# cnc_1_0_0.net
KiCad netlist of a schematic drawn in EAGLE
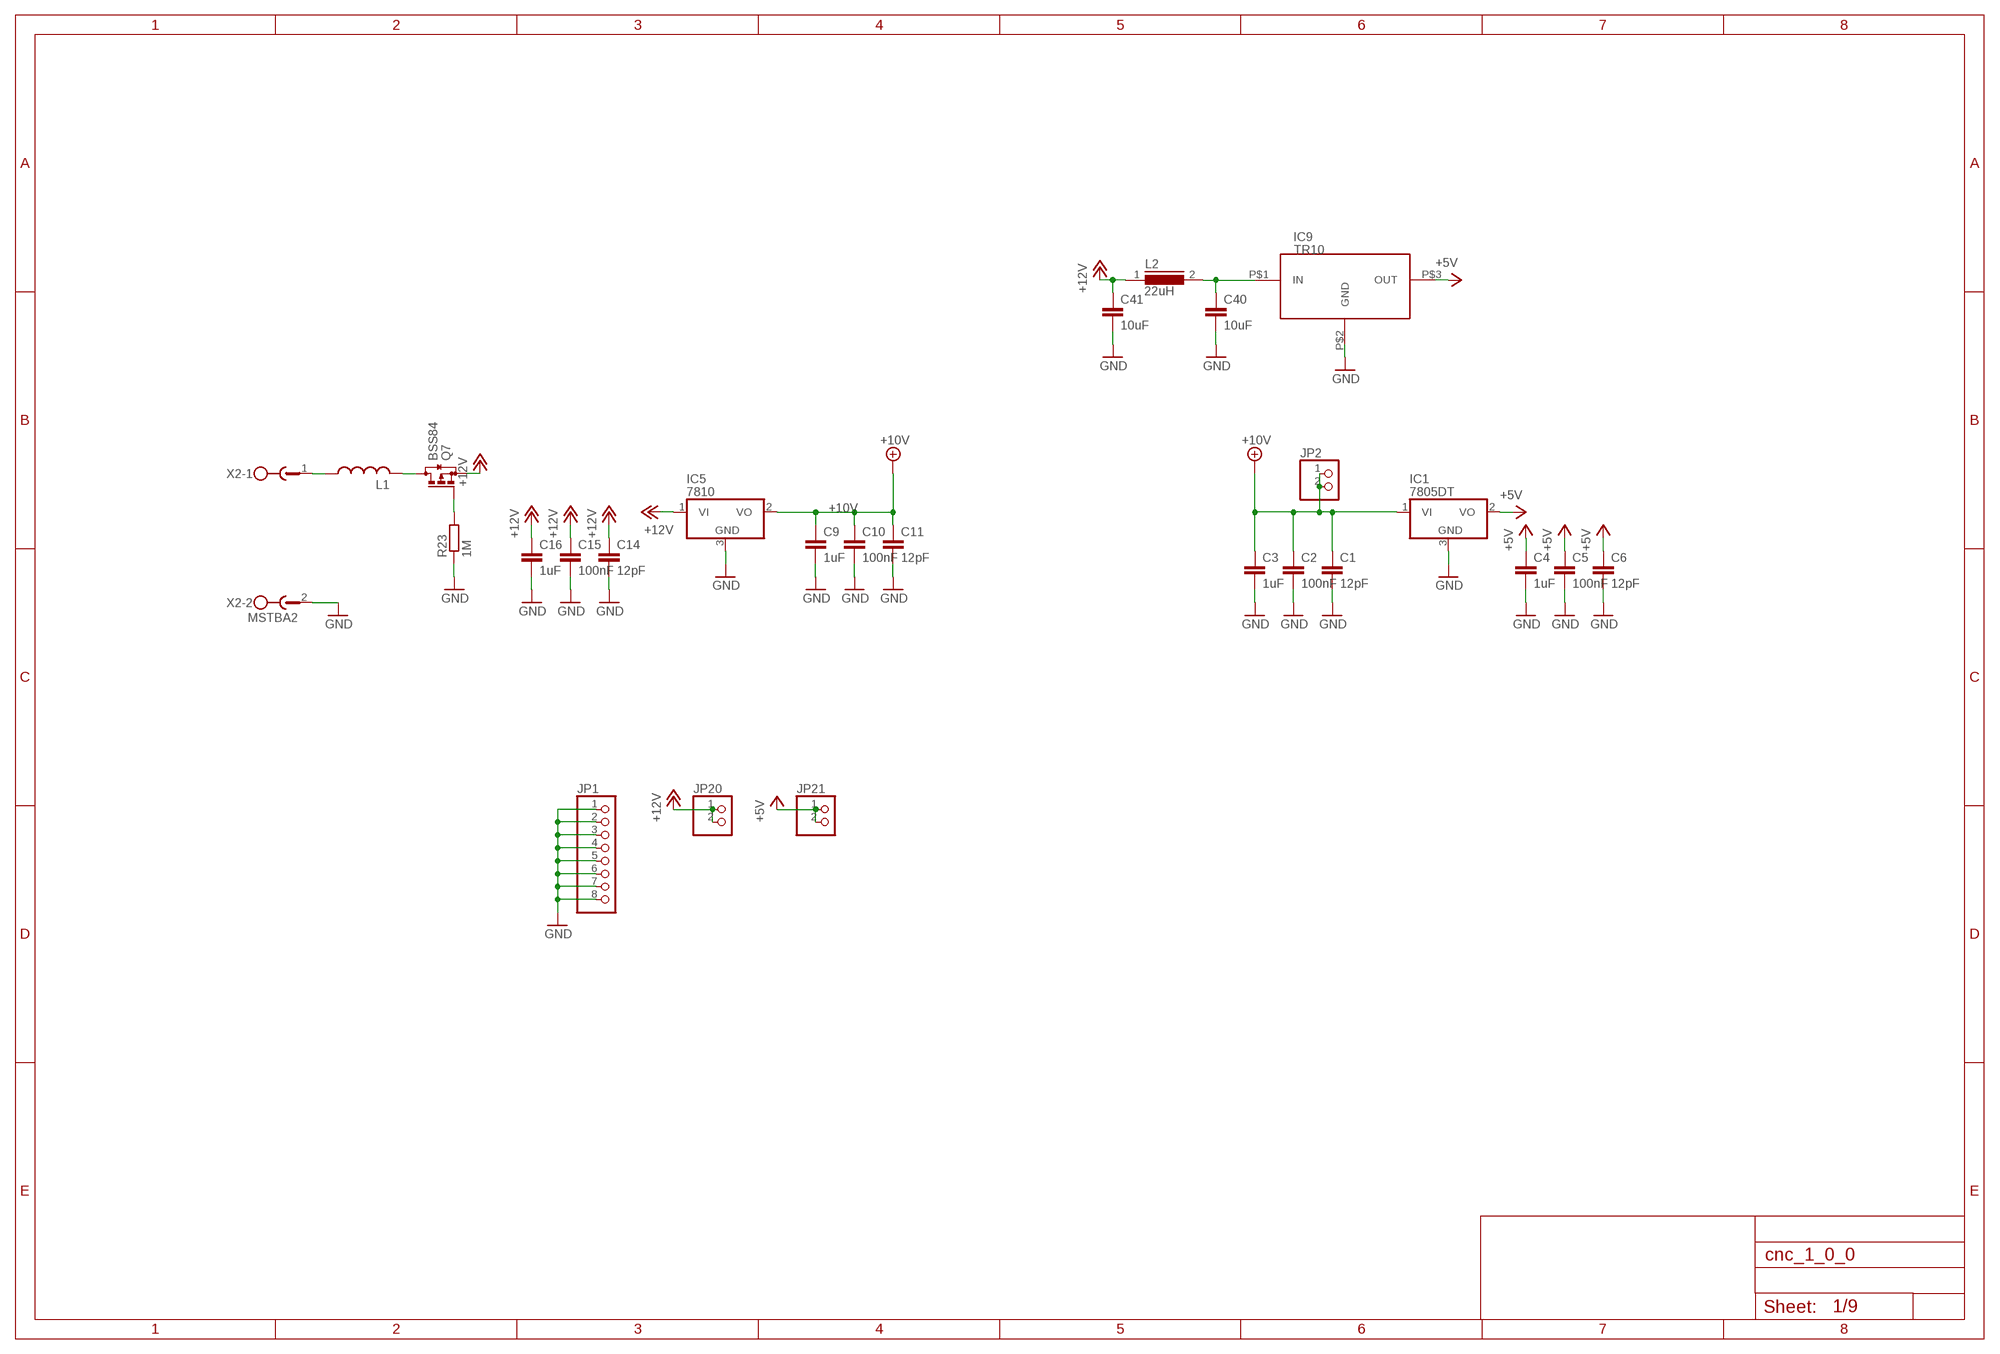
[diagram p0: schematic, sheet 1]
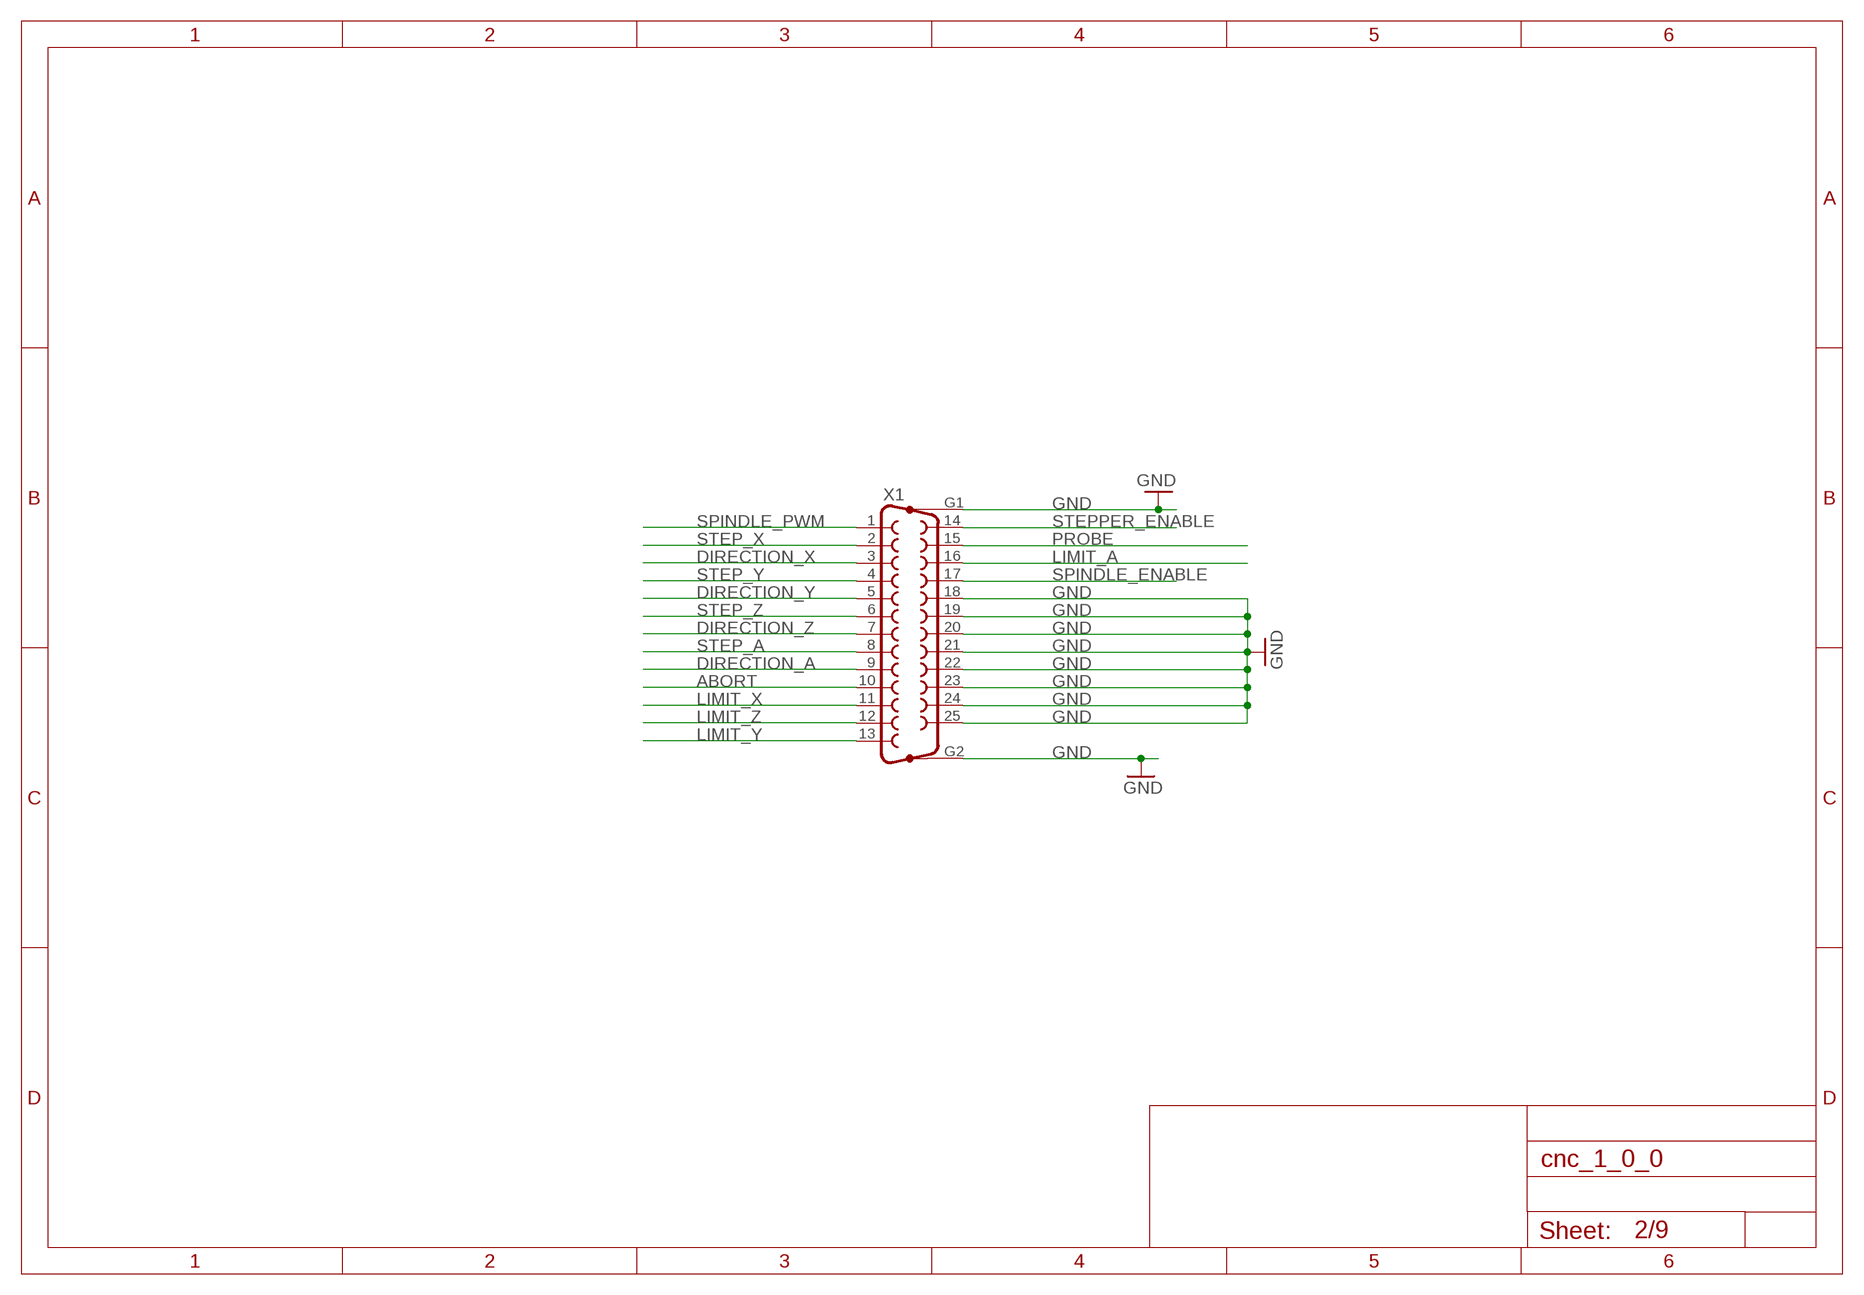
[diagram p1: schematic, sheet 2]
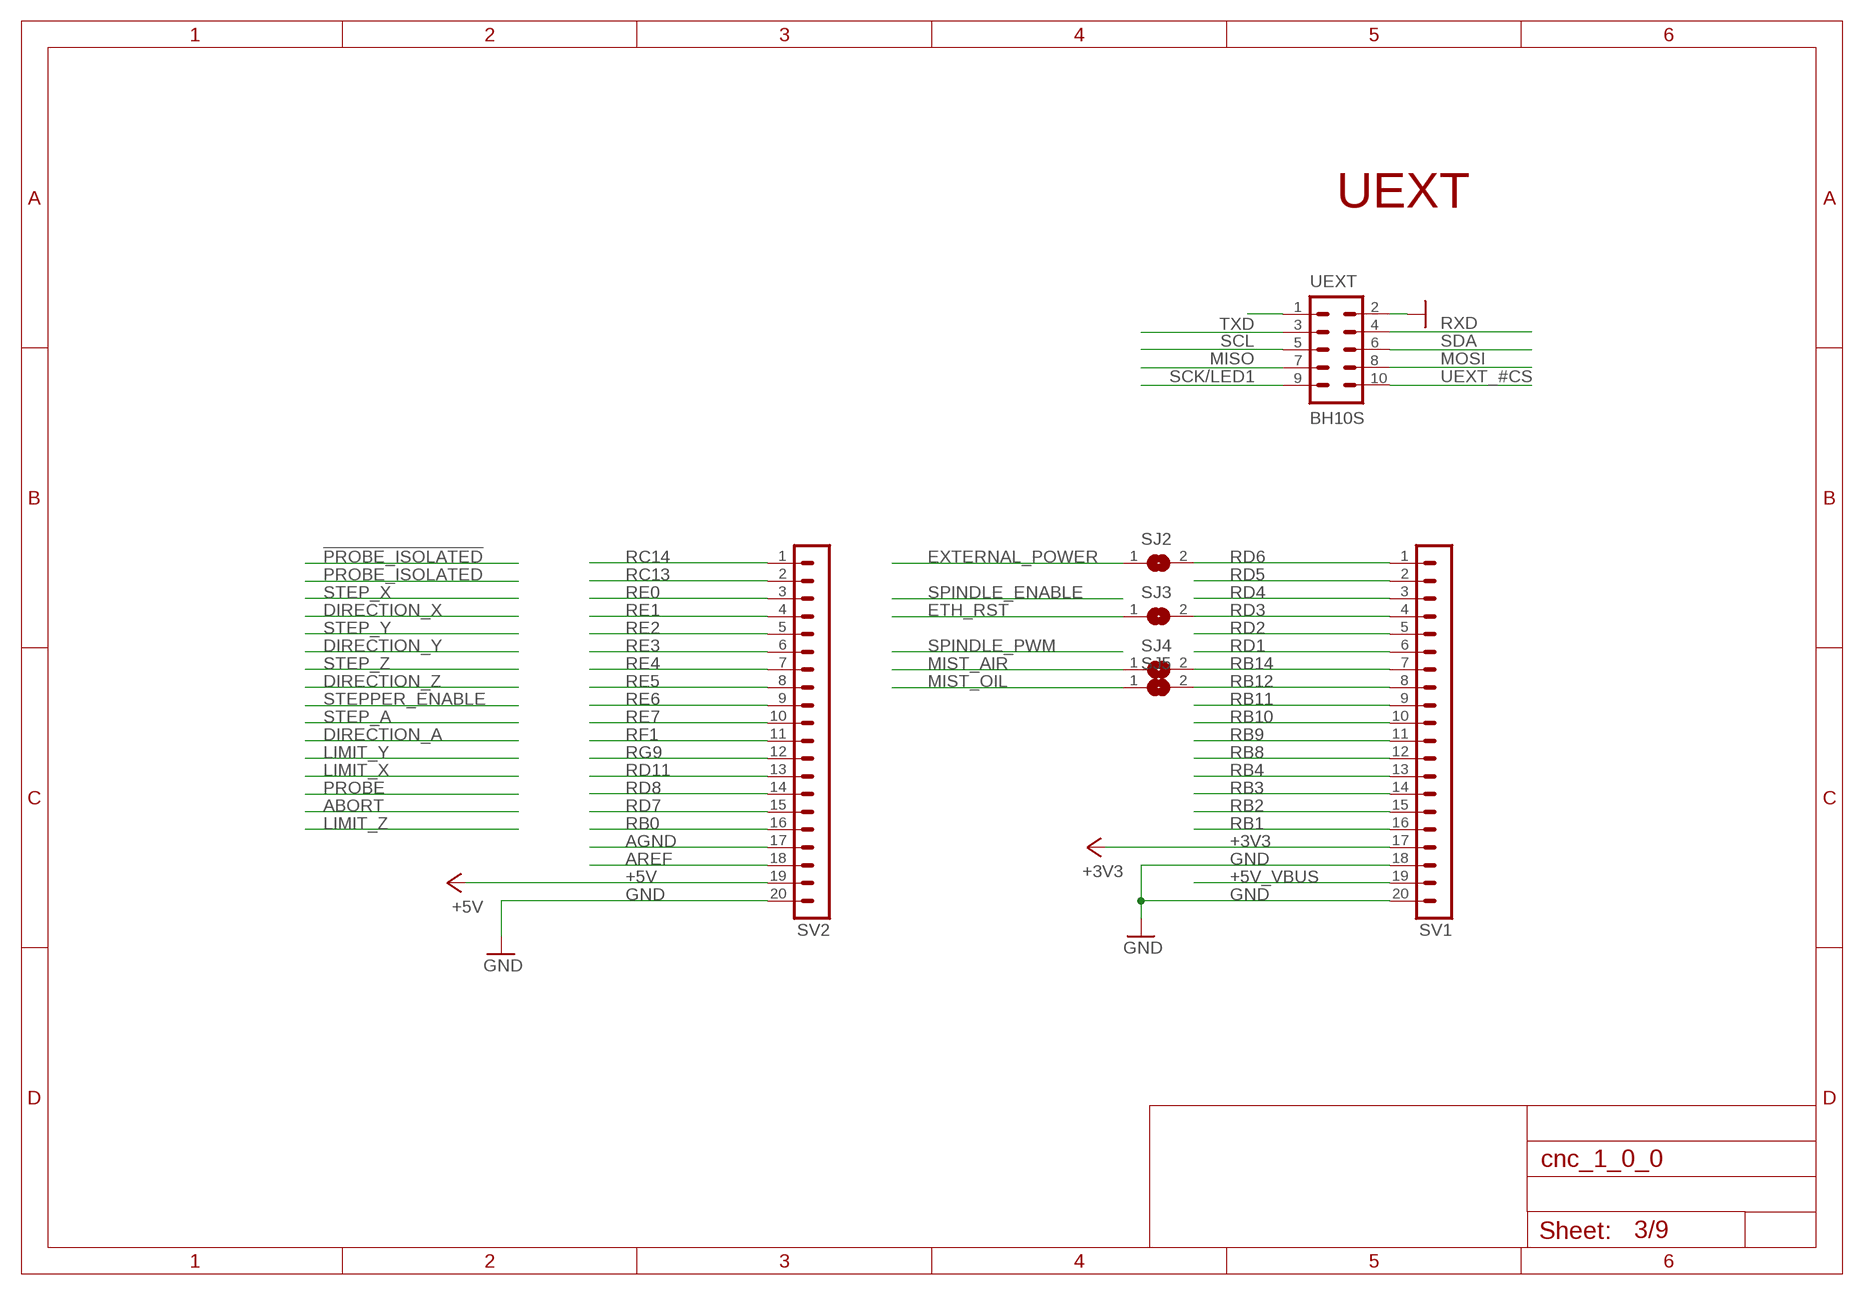
[diagram p2: schematic, sheet 3]
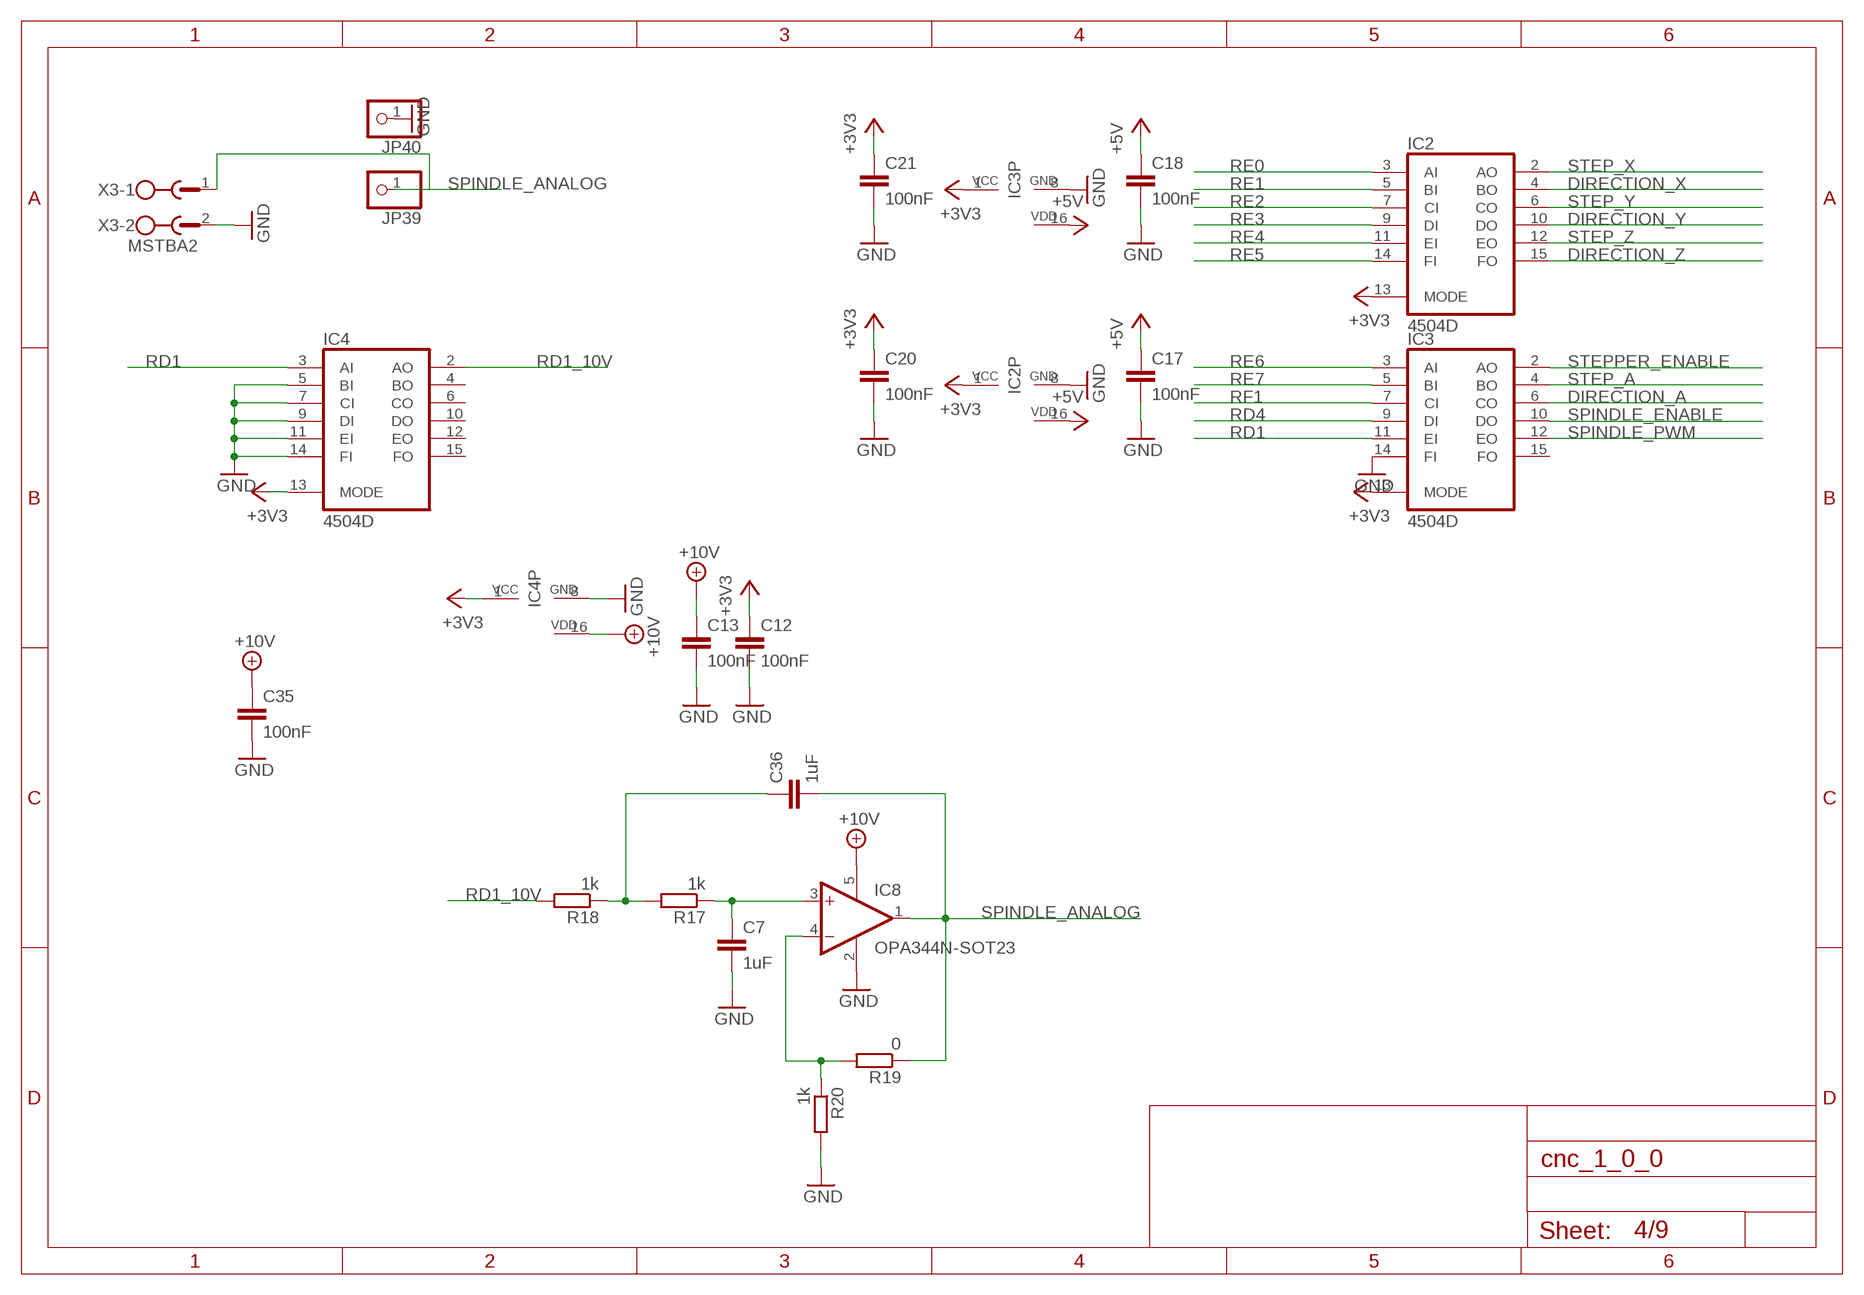
[diagram p3: schematic, sheet 4]
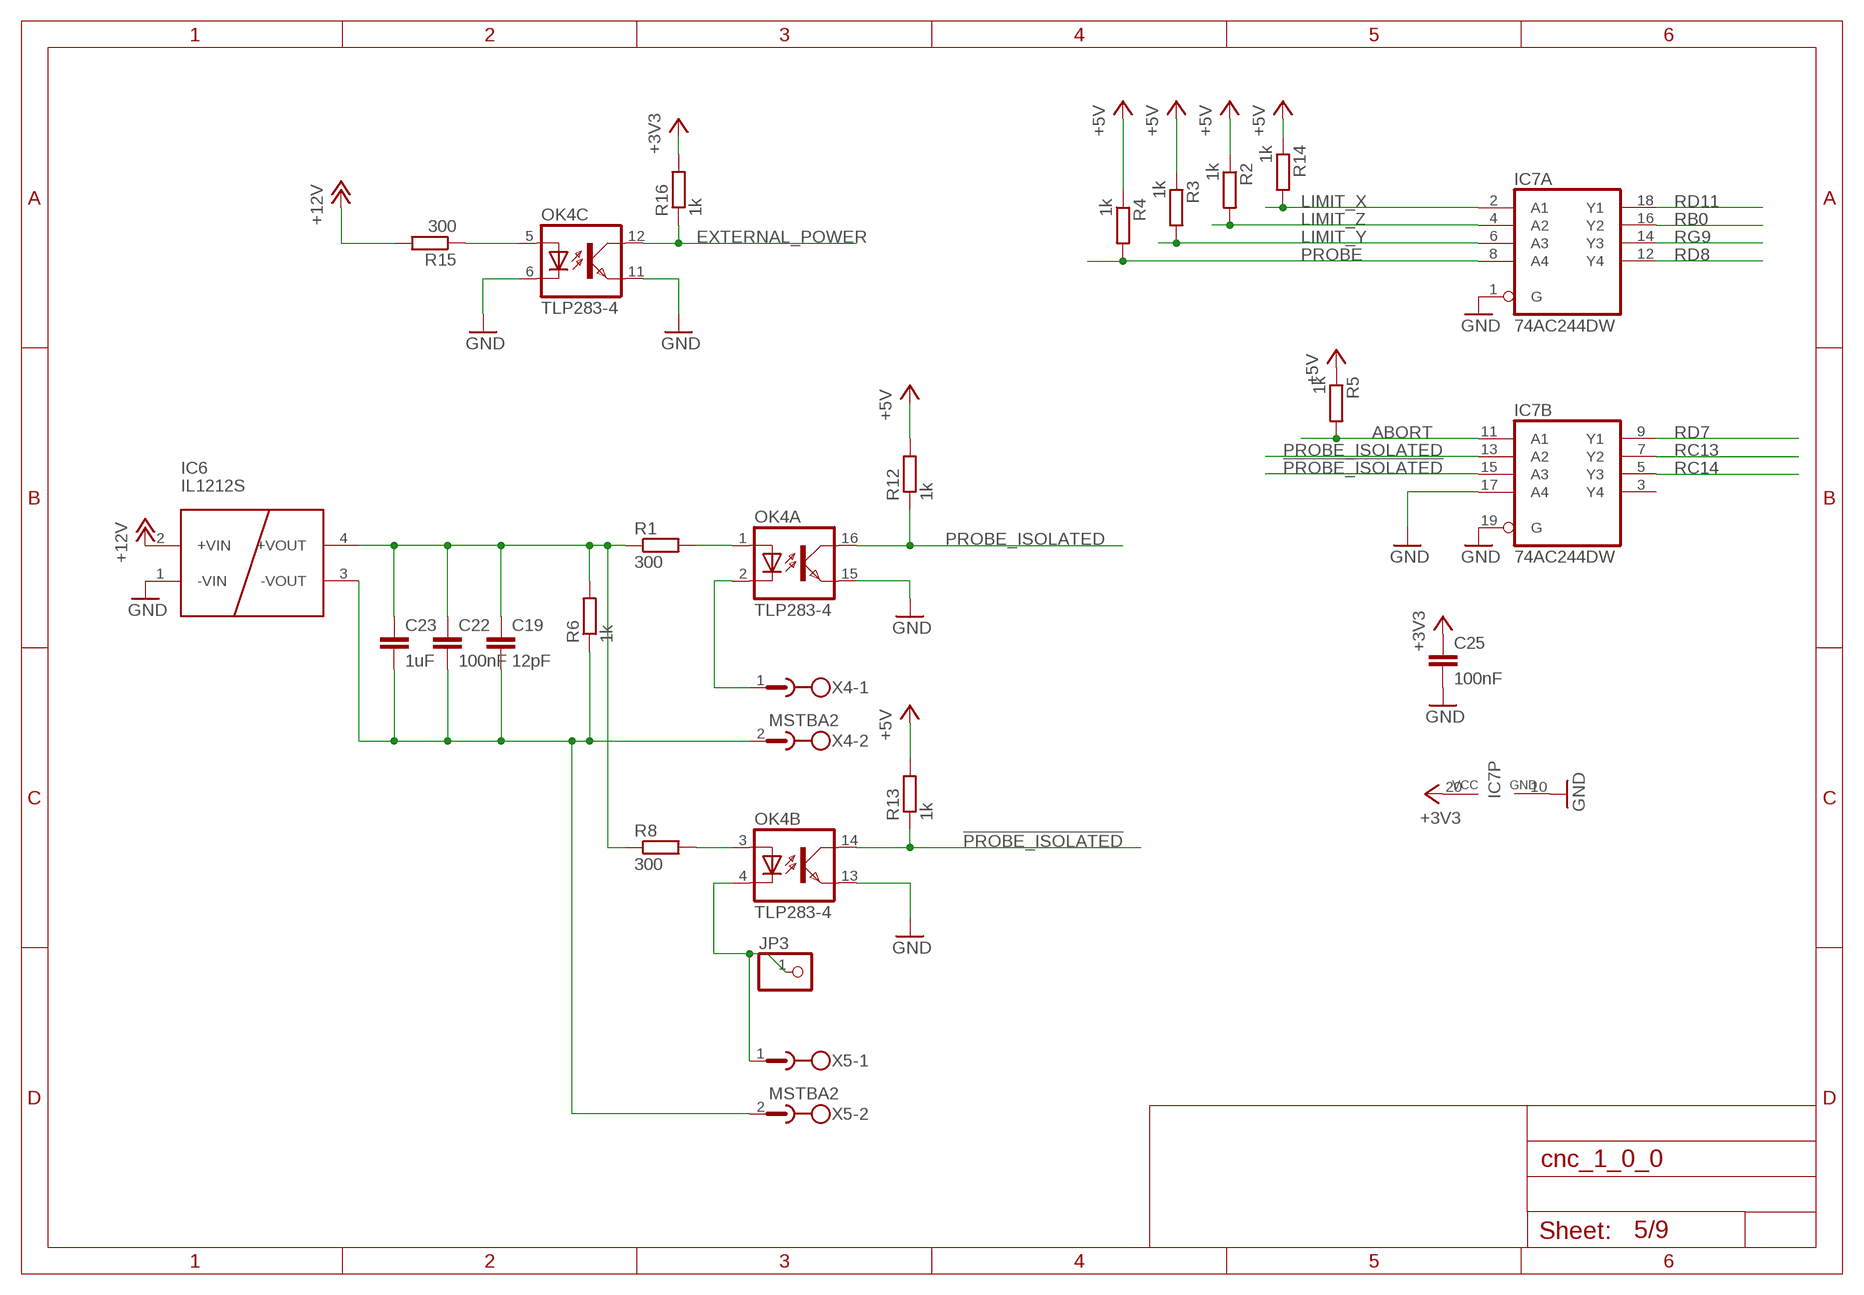
[diagram p4: schematic, sheet 5]
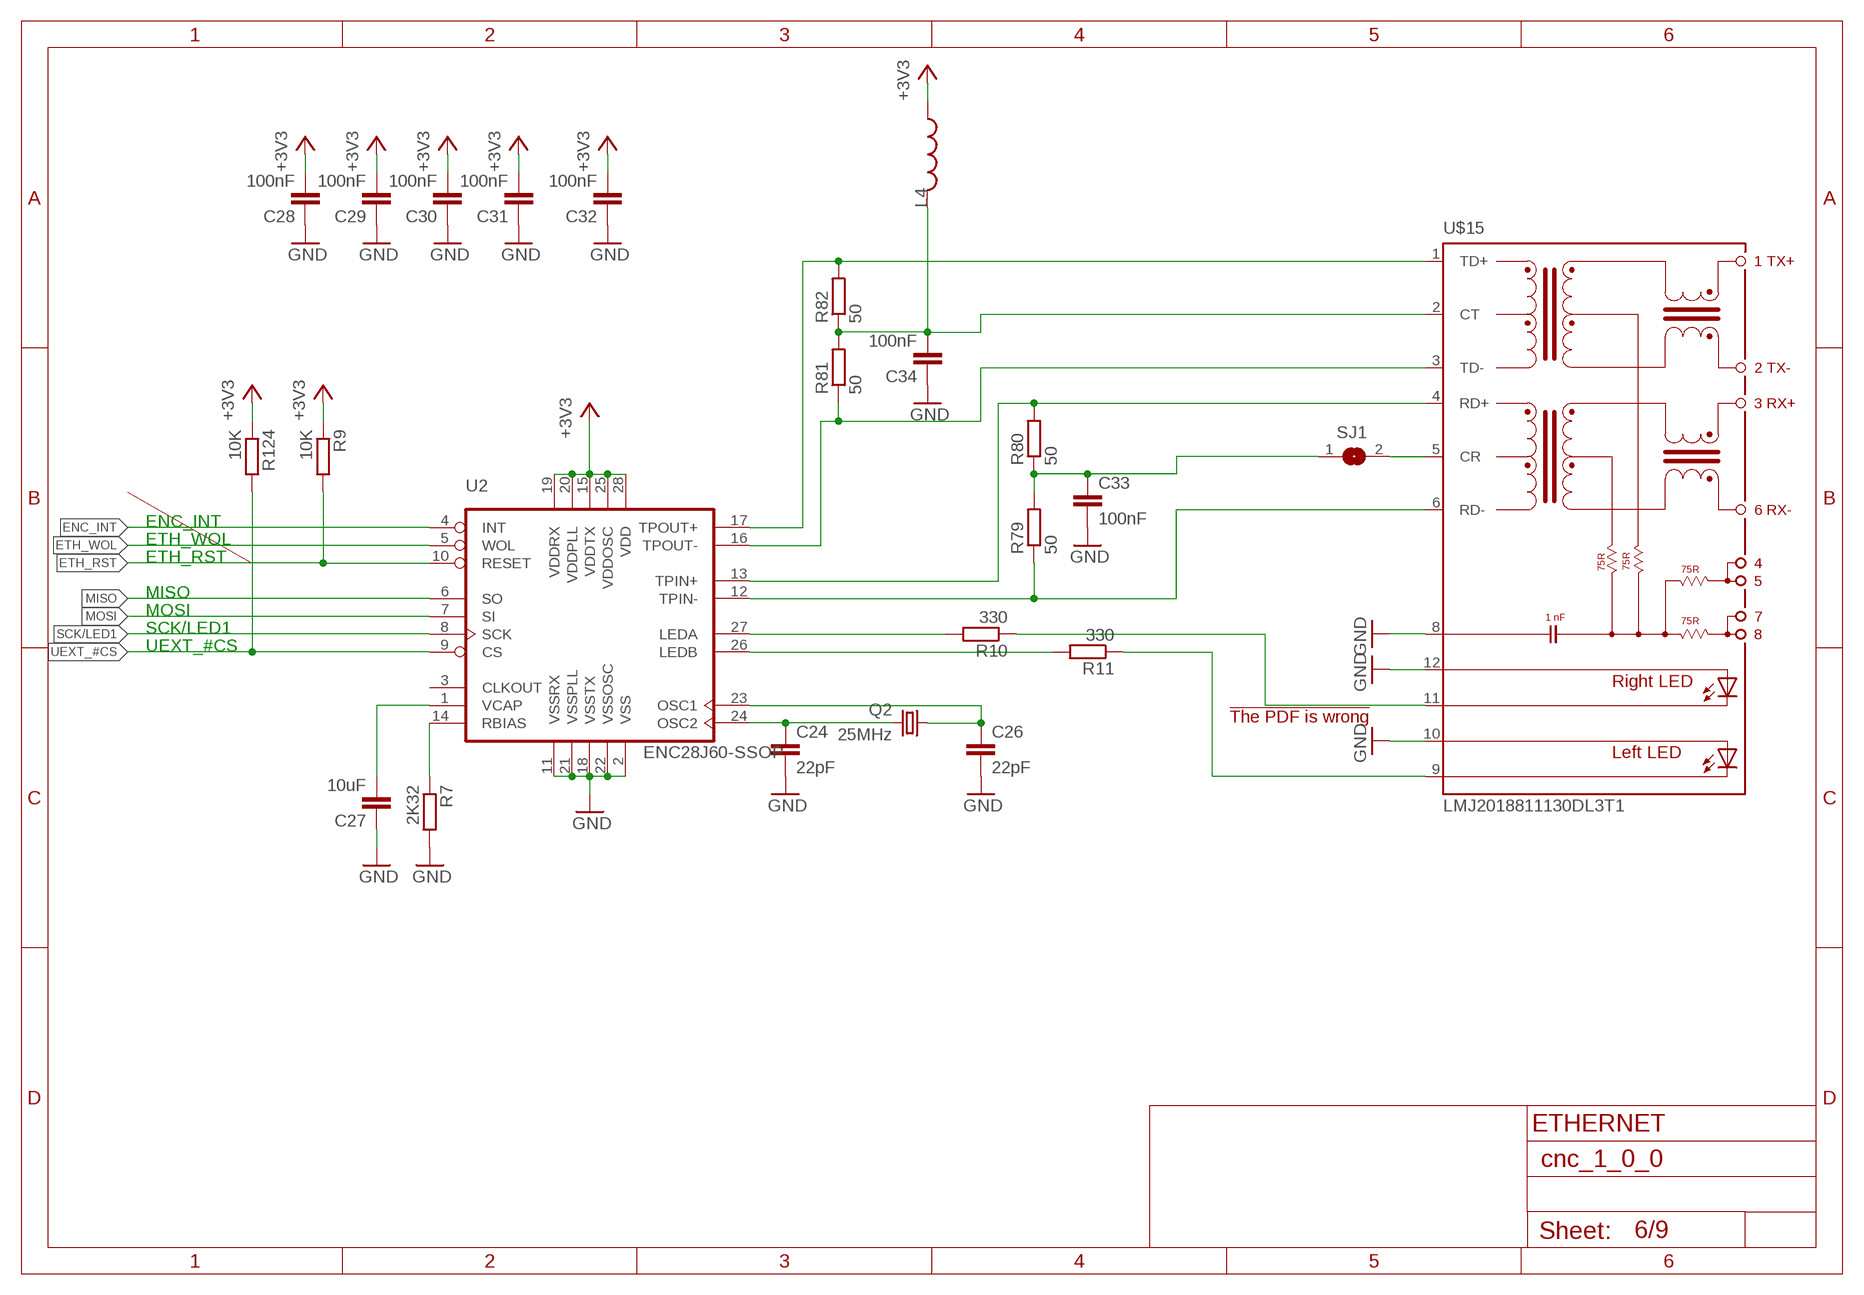
[diagram p5: schematic, sheet 6]
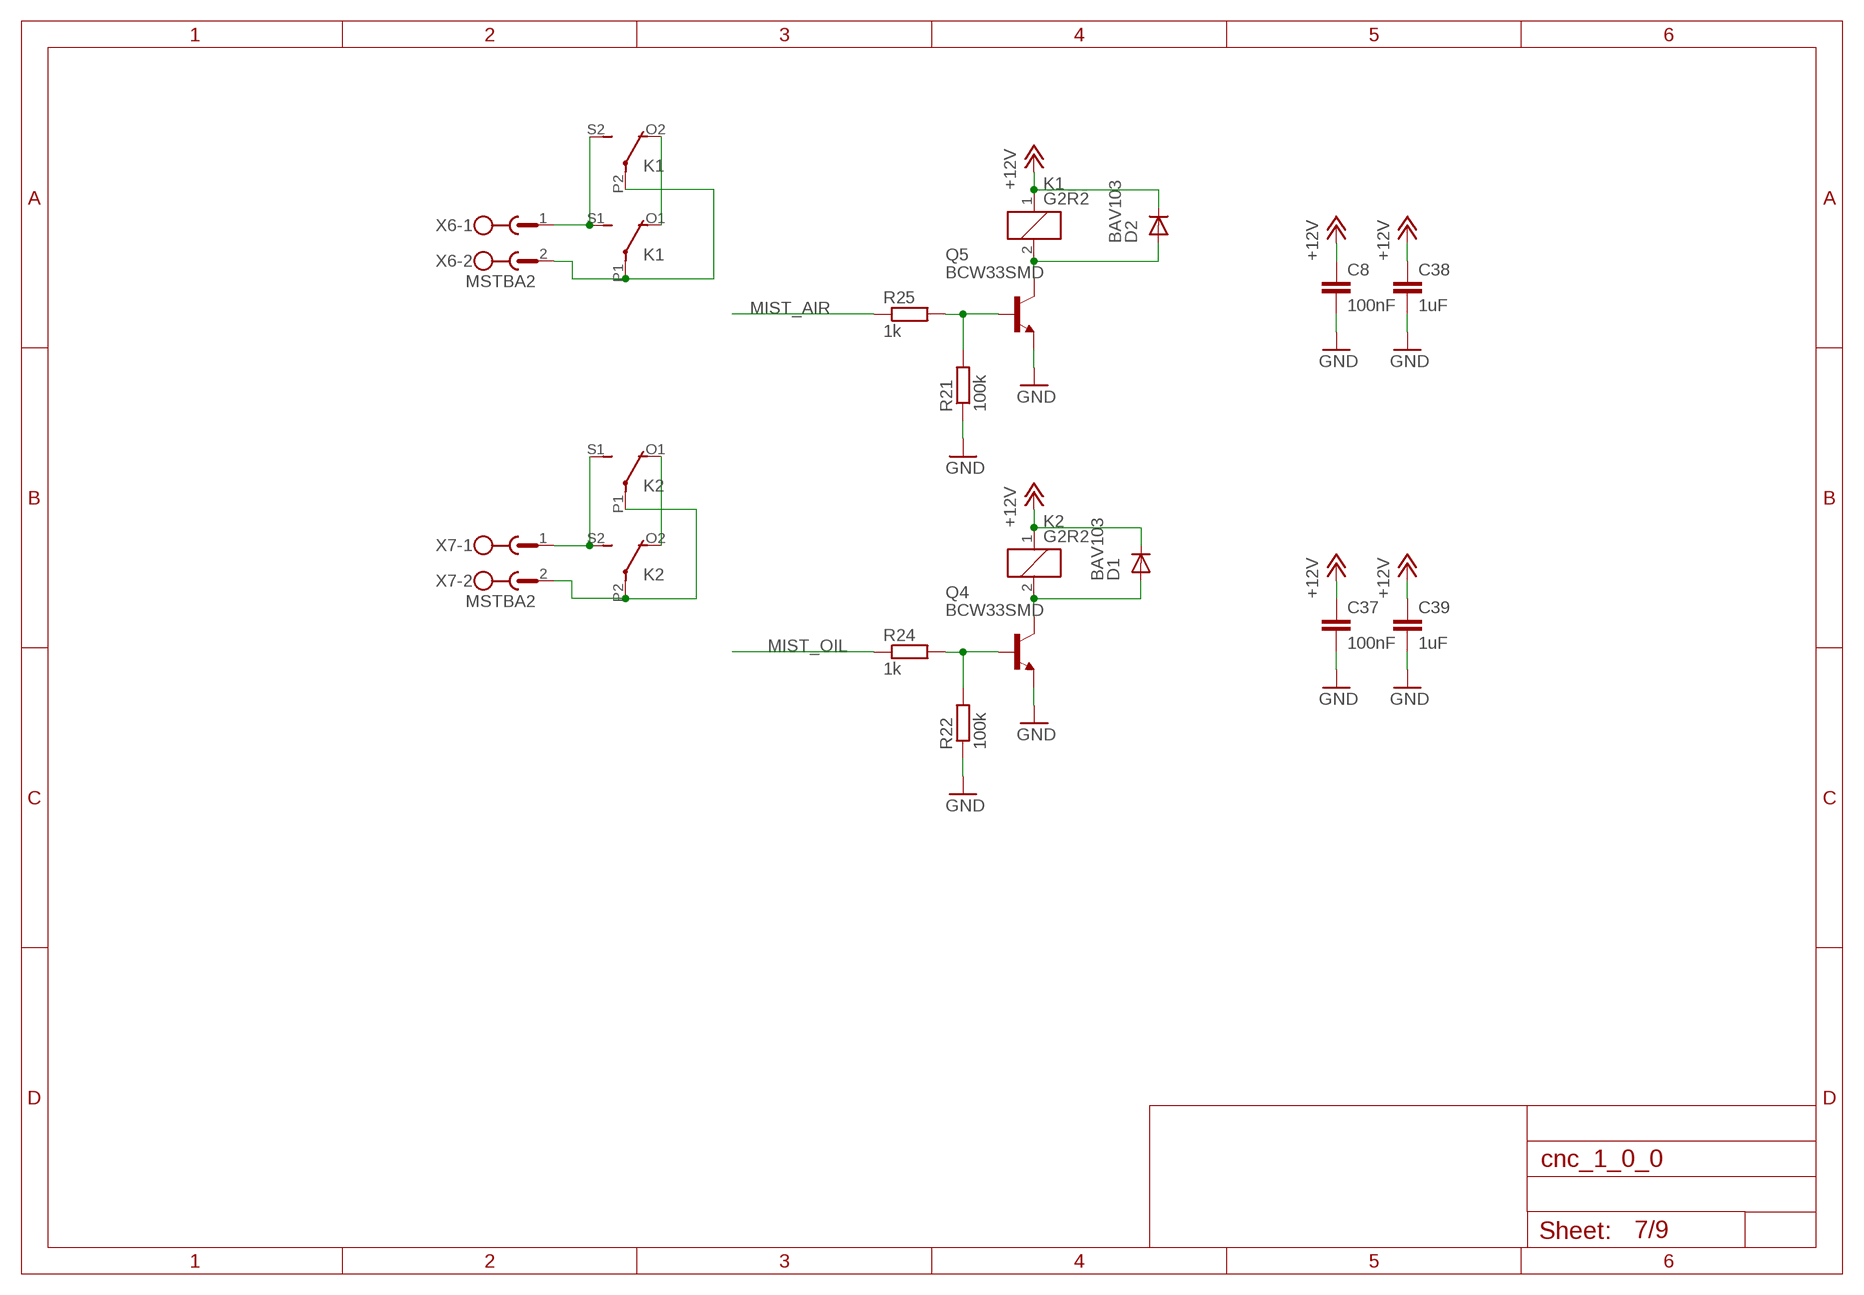
[diagram p6: schematic, sheet 7]
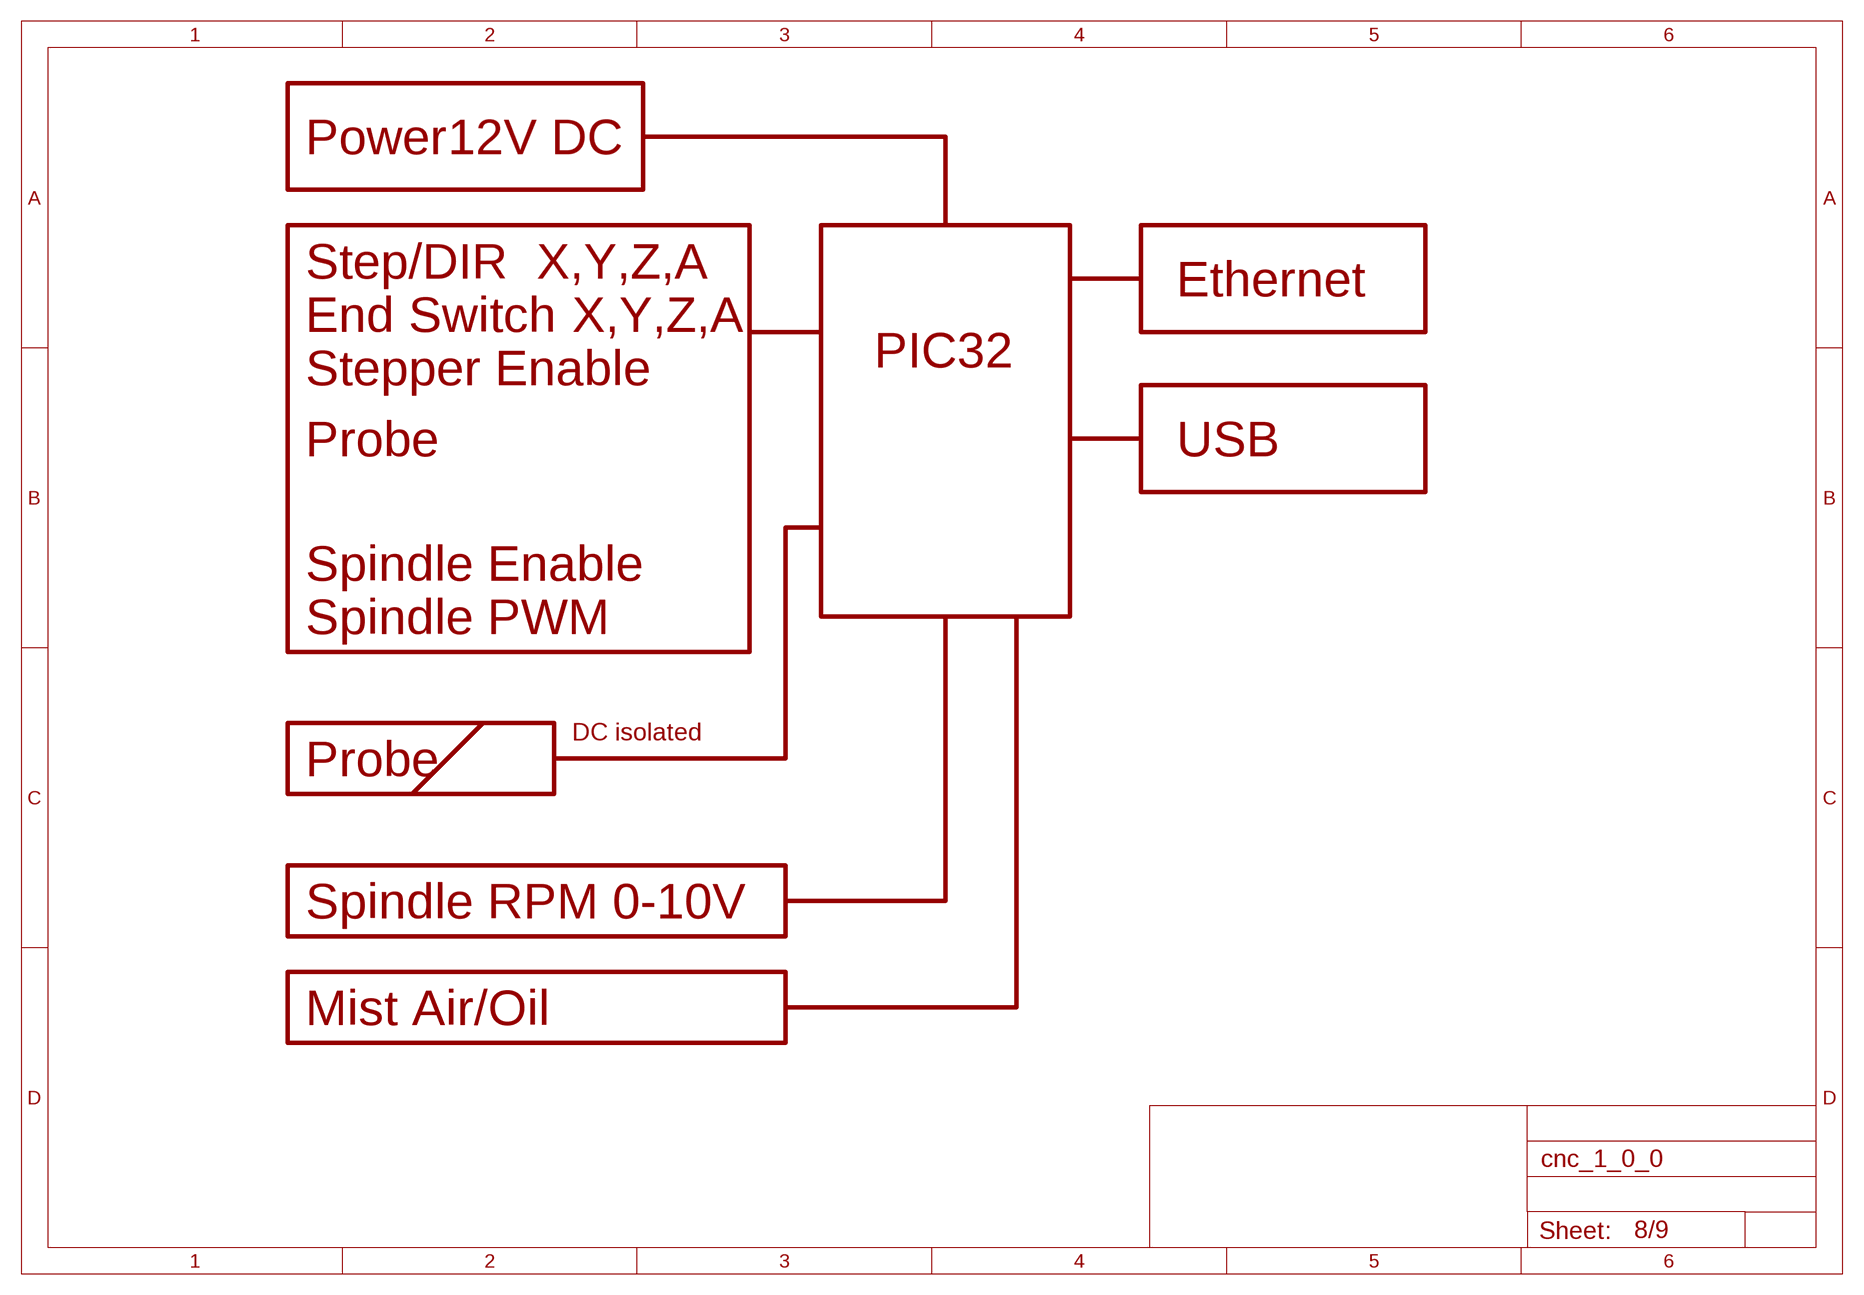
[diagram p7: schematic, sheet 8]
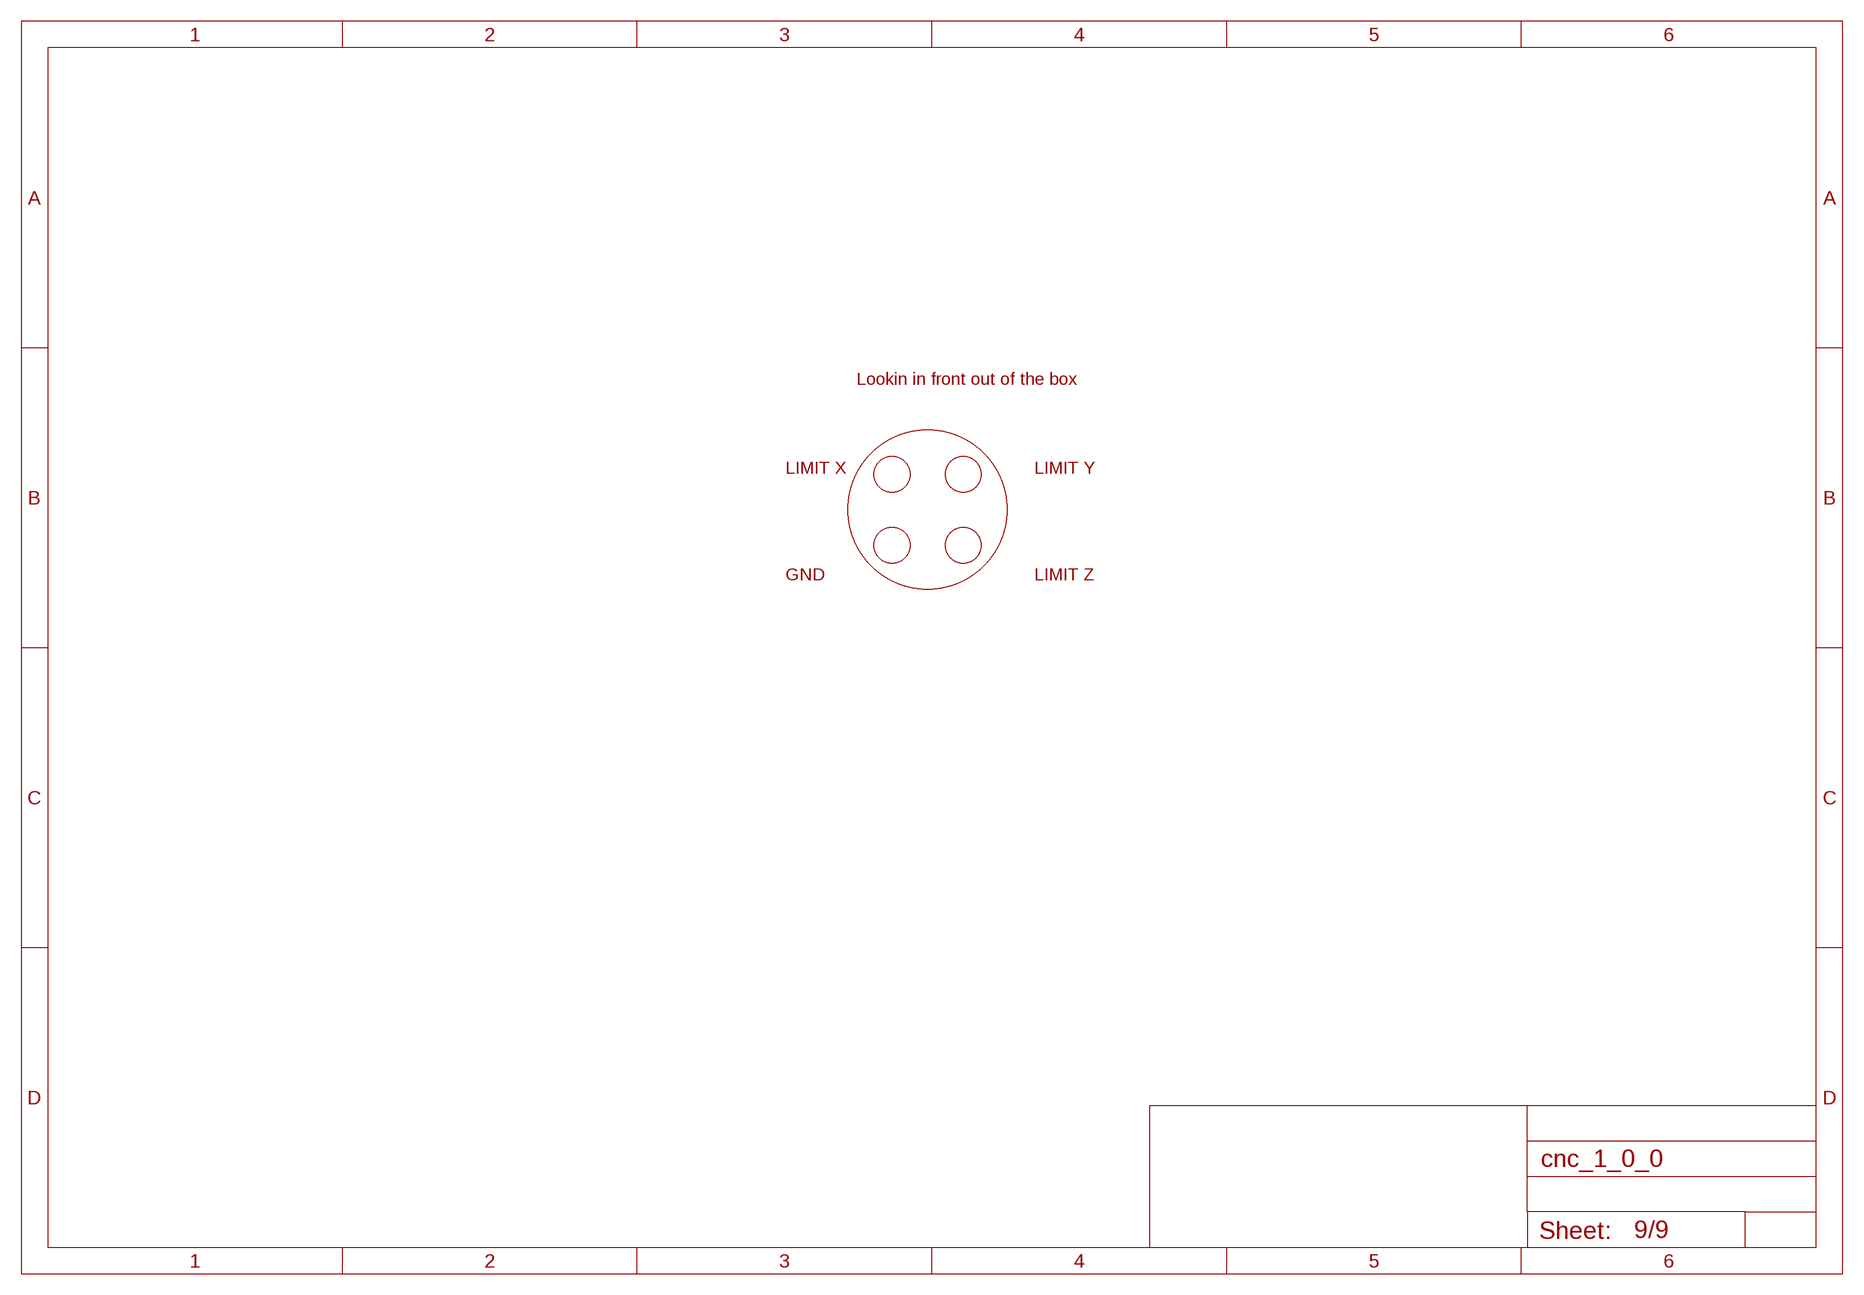
[diagram p8: schematic, sheet 9]

(export (version "E")
  (design (tool "Eeschema 10.0.6"))
  (components
    (comp (ref "SJ2") (value "SJ") (footprint "eagle-import:SJ") (libsource (lib "eagle-import") (part "SJ")))
    (comp (ref "SJ3") (value "SJ") (footprint "eagle-import:SJ") (libsource (lib "eagle-import") (part "SJ")))
    (comp (ref "SJ4") (value "SJ") (footprint "eagle-import:SJ") (libsource (lib "eagle-import") (part "SJ")))
    (comp (ref "SJ5") (value "SJ") (footprint "eagle-import:SJ") (libsource (lib "eagle-import") (part "SJ")))
    (comp (ref "SV1")
      (value "MA20-1")
      (footprint "eagle-import:MA20-1")
      (libsource (lib "eagle-import") (part "MA20-1"))
    )
    (comp (ref "SV2")
      (value "MA20-1")
      (footprint "eagle-import:MA20-1")
      (libsource (lib "eagle-import") (part "MA20-1"))
    )
    (comp (ref "UEXT")
      (value "BH10S")
      (footprint "eagle-import:ML10-MALE")
      (libsource (lib "eagle-import") (part "ML10"))
    )
    (comp (ref "C19")
      (value "12pF")
      (footprint "eagle-import:C0805K")
      (libsource (lib "eagle-import") (part "C-EUC0805K"))
    )
    (comp (ref "C22")
      (value "100nF")
      (footprint "eagle-import:C0805K")
      (libsource (lib "eagle-import") (part "C-EUC0805K"))
    )
    (comp (ref "C23")
      (value "1uF")
      (footprint "eagle-import:C0805K")
      (libsource (lib "eagle-import") (part "C-EUC0805K"))
    )
    (comp (ref "C25")
      (value "100nF")
      (footprint "eagle-import:C0805K")
      (libsource (lib "eagle-import") (part "C-EUC0805K"))
    )
    (comp (ref "IC6")
      (value "IL1212S")
      (footprint "eagle-import:SIL4")
      (libsource (lib "eagle-import") (part "IL0512S"))
    )
    (comp (ref "IC7")
      (value "74AC244DW")
      (footprint "eagle-import:SO20W")
      (libsource (lib "eagle-import") (part "74244DWAC"))
    )
    (comp (ref "JP3")
      (value "PINHD-1X1")
      (footprint "eagle-import:1X01")
      (libsource (lib "eagle-import") (part "PINHD-1X1"))
    )
    (comp (ref "OK4")
      (value "TLP283-4")
      (footprint "eagle-import:MINI-FLAT-16")
      (libsource (lib "eagle-import") (part "TLP283-4"))
    )
    (comp (ref "R1")
      (value "300")
      (footprint "eagle-import:R0805")
      (libsource (lib "eagle-import") (part "R-EU_R0805"))
    )
    (comp (ref "R2")
      (value "1k")
      (footprint "eagle-import:R0805")
      (libsource (lib "eagle-import") (part "R-EU_R0805"))
    )
    (comp (ref "R3")
      (value "1k")
      (footprint "eagle-import:R0805")
      (libsource (lib "eagle-import") (part "R-EU_R0805"))
    )
    (comp (ref "R4")
      (value "1k")
      (footprint "eagle-import:R0805")
      (libsource (lib "eagle-import") (part "R-EU_R0805"))
    )
    (comp (ref "R5")
      (value "1k")
      (footprint "eagle-import:R0805")
      (libsource (lib "eagle-import") (part "R-EU_R0805"))
    )
    (comp (ref "R6")
      (value "1k")
      (footprint "eagle-import:R0805")
      (libsource (lib "eagle-import") (part "R-EU_R0805"))
    )
    (comp (ref "R8")
      (value "300")
      (footprint "eagle-import:R0805")
      (libsource (lib "eagle-import") (part "R-EU_R0805"))
    )
    (comp (ref "R12")
      (value "1k")
      (footprint "eagle-import:R0805")
      (libsource (lib "eagle-import") (part "R-EU_R0805"))
    )
    (comp (ref "R13")
      (value "1k")
      (footprint "eagle-import:R0805")
      (libsource (lib "eagle-import") (part "R-EU_R0805"))
    )
    (comp (ref "R14")
      (value "1k")
      (footprint "eagle-import:R0805")
      (libsource (lib "eagle-import") (part "R-EU_R0805"))
    )
    (comp (ref "R15")
      (value "300")
      (footprint "eagle-import:R0805")
      (libsource (lib "eagle-import") (part "R-EU_R0805"))
    )
    (comp (ref "R16")
      (value "1k")
      (footprint "eagle-import:R0805")
      (libsource (lib "eagle-import") (part "R-EU_R0805"))
    )
    (comp (ref "X4")
      (value "MSTBA2")
      (footprint "eagle-import:MSTBA2")
      (fields
        (field (name "MF") "FARNELL")
        (field (name "MPN") "1757242")
        (field (name "MF_1") "FARNELL")
        (field (name "MPN_1") "1757242")
        (field (name "OC_FARNELL") "3705171")
        (field (name "OC_NEWARK") "71C4161")
      )
      (libsource (lib "eagle-import") (part "MSTBA2"))
    )
    (comp (ref "X5")
      (value "MSTBA2")
      (footprint "eagle-import:MSTBA2")
      (fields (field (name "MF") "FARNELL") (field (name "MPN") "1757242"))
      (libsource (lib "eagle-import") (part "MSTBA2"))
    )
    (comp (ref "C24")
      (value "22pF")
      (footprint "eagle-import:C0603")
      (libsource (lib "eagle-import") (part "C-EUC0603"))
    )
    (comp (ref "C26")
      (value "22pF")
      (footprint "eagle-import:C0603")
      (libsource (lib "eagle-import") (part "C-EUC0603"))
    )
    (comp (ref "C27")
      (value "10uF")
      (footprint "eagle-import:C0805K")
      (libsource (lib "eagle-import") (part "C-EUC0805K"))
    )
    (comp (ref "C28")
      (value "100nF")
      (footprint "eagle-import:C0603")
      (libsource (lib "eagle-import") (part "C-EUC0603"))
    )
    (comp (ref "C29")
      (value "100nF")
      (footprint "eagle-import:C0603")
      (libsource (lib "eagle-import") (part "C-EUC0603"))
    )
    (comp (ref "C30")
      (value "100nF")
      (footprint "eagle-import:C0603")
      (libsource (lib "eagle-import") (part "C-EUC0603"))
    )
    (comp (ref "C31")
      (value "100nF")
      (footprint "eagle-import:C0603")
      (libsource (lib "eagle-import") (part "C-EUC0603"))
    )
    (comp (ref "C32")
      (value "100nF")
      (footprint "eagle-import:C0603")
      (libsource (lib "eagle-import") (part "C-EUC0603"))
    )
    (comp (ref "C33")
      (value "100nF")
      (footprint "eagle-import:C0603")
      (libsource (lib "eagle-import") (part "C-EUC0603"))
    )
    (comp (ref "C34")
      (value "100nF")
      (footprint "eagle-import:C0603")
      (libsource (lib "eagle-import") (part "C-EUC0603"))
    )
    (comp (ref "L4")
      (value "INDUCTOR0603")
      (footprint "eagle-import:0603")
      (libsource (lib "eagle-import") (part "INDUCTOR0603"))
    )
    (comp (ref "Q2")
      (value "25MHz")
      (footprint "eagle-import:CRYSTAL-SMD-5X3")
      (libsource (lib "eagle-import") (part "CRYSTAL5X3"))
    )
    (comp (ref "R7")
      (value "2K32")
      (footprint "eagle-import:R0805")
      (libsource (lib "eagle-import") (part "R-EU_R0805"))
    )
    (comp (ref "R9")
      (value "10K")
      (footprint "eagle-import:R0805")
      (libsource (lib "eagle-import") (part "R-EU_R0805"))
    )
    (comp (ref "R10")
      (value "330")
      (footprint "eagle-import:R0805")
      (libsource (lib "eagle-import") (part "R-EU_R0805"))
    )
    (comp (ref "R11")
      (value "330")
      (footprint "eagle-import:R0805")
      (libsource (lib "eagle-import") (part "R-EU_R0805"))
    )
    (comp (ref "R79")
      (value "50")
      (footprint "eagle-import:R0603")
      (libsource (lib "eagle-import") (part "R-EU_R0603"))
    )
    (comp (ref "R80")
      (value "50")
      (footprint "eagle-import:R0603")
      (libsource (lib "eagle-import") (part "R-EU_R0603"))
    )
    (comp (ref "R81")
      (value "50")
      (footprint "eagle-import:R0603")
      (libsource (lib "eagle-import") (part "R-EU_R0603"))
    )
    (comp (ref "R82")
      (value "50")
      (footprint "eagle-import:R0603")
      (libsource (lib "eagle-import") (part "R-EU_R0603"))
    )
    (comp (ref "R124")
      (value "10K")
      (footprint "eagle-import:R0805")
      (libsource (lib "eagle-import") (part "R-EU_R0805"))
    )
    (comp (ref "SJ1") (value "SJ") (footprint "eagle-import:SJ") (libsource (lib "eagle-import") (part "SJ")))
    (comp (ref "U$15")
      (value "LMJ2018811130DL3T1")
      (footprint "eagle-import:AMPHENOL-LMJ2018814100DL2T1B_RJ45")
      (libsource (lib "eagle-import") (part "AMPHENOL-LMJ2018814100DL2T1B_LMJ2018814100DL"))
    )
    (comp (ref "U2")
      (value "ENC28J60-SSOP")
      (footprint "eagle-import:SSOP28")
      (libsource (lib "eagle-import") (part "ENC28J60-SSOP"))
    )
    (comp (ref "C8")
      (value "100nF")
      (footprint "eagle-import:C0805K")
      (libsource (lib "eagle-import") (part "C-EUC0805K"))
    )
    (comp (ref "C37")
      (value "100nF")
      (footprint "eagle-import:C0805K")
      (libsource (lib "eagle-import") (part "C-EUC0805K"))
    )
    (comp (ref "C38")
      (value "1uF")
      (footprint "eagle-import:C0805K")
      (libsource (lib "eagle-import") (part "C-EUC0805K"))
    )
    (comp (ref "C39")
      (value "1uF")
      (footprint "eagle-import:C0805K")
      (libsource (lib "eagle-import") (part "C-EUC0805K"))
    )
    (comp (ref "D1")
      (value "BAV103")
      (footprint "eagle-import:MINIMELF")
      (libsource (lib "eagle-import") (part "DIODE-MINIMELF"))
    )
    (comp (ref "D2")
      (value "BAV103")
      (footprint "eagle-import:MINIMELF")
      (libsource (lib "eagle-import") (part "DIODE-MINIMELF"))
    )
    (comp (ref "K1")
      (value "G2R2")
      (footprint "eagle-import:G2R2")
      (fields
        (field (name "MF") "OMRON COMPONENTS USA")
        (field (name "MPN") "G2R-2-DC6")
        (field (name "MF_1") "OMRON COMPONENTS USA")
        (field (name "MPN_1") "G2R-2-DC6")
        (field (name "OC_FARNELL") "unknown")
        (field (name "OC_NEWARK") "89C5317")
      )
      (libsource (lib "eagle-import") (part "G2R2"))
    )
    (comp (ref "K2")
      (value "G2R2")
      (footprint "eagle-import:G2R2")
      (fields
        (field (name "MF") "OMRON COMPONENTS USA")
        (field (name "MPN") "G2R-2-DC6")
        (field (name "MF_1") "OMRON COMPONENTS USA")
        (field (name "MPN_1") "G2R-2-DC6")
        (field (name "OC_FARNELL") "unknown")
        (field (name "OC_NEWARK") "89C5317")
      )
      (libsource (lib "eagle-import") (part "G2R2"))
    )
    (comp (ref "Q4")
      (value "BCW33SMD")
      (footprint "eagle-import:SOT23-BEC")
      (libsource (lib "eagle-import") (part "BCW33SMD"))
    )
    (comp (ref "Q5")
      (value "BCW33SMD")
      (footprint "eagle-import:SOT23-BEC")
      (libsource (lib "eagle-import") (part "BCW33SMD"))
    )
    (comp (ref "R21")
      (value "100k")
      (footprint "eagle-import:R0805")
      (libsource (lib "eagle-import") (part "R-EU_R0805"))
    )
    (comp (ref "R22")
      (value "100k")
      (footprint "eagle-import:R0805")
      (libsource (lib "eagle-import") (part "R-EU_R0805"))
    )
    (comp (ref "R24")
      (value "1k")
      (footprint "eagle-import:R0805")
      (libsource (lib "eagle-import") (part "R-EU_R0805"))
    )
    (comp (ref "R25")
      (value "1k")
      (footprint "eagle-import:R0805")
      (libsource (lib "eagle-import") (part "R-EU_R0805"))
    )
    (comp (ref "X6")
      (value "MSTBA2")
      (footprint "eagle-import:MSTBA2")
      (fields
        (field (name "MF") "FARNELL")
        (field (name "MPN") "1757242")
        (field (name "MF_1") "FARNELL")
        (field (name "MPN_1") "1757242")
        (field (name "OC_FARNELL") "3705171")
        (field (name "OC_NEWARK") "71C4161")
      )
      (libsource (lib "eagle-import") (part "MSTBA2"))
    )
    (comp (ref "X7")
      (value "MSTBA2")
      (footprint "eagle-import:MSTBA2")
      (fields
        (field (name "MF") "FARNELL")
        (field (name "MPN") "1757242")
        (field (name "MF_1") "FARNELL")
        (field (name "MPN_1") "1757242")
        (field (name "OC_FARNELL") "3705171")
        (field (name "OC_NEWARK") "71C4161")
      )
      (libsource (lib "eagle-import") (part "MSTBA2"))
    )
    (comp (ref "C7")
      (value "1uF")
      (footprint "eagle-import:C0805K")
      (libsource (lib "eagle-import") (part "C-EUC0805K"))
    )
    (comp (ref "C12")
      (value "100nF")
      (footprint "eagle-import:C0805K")
      (libsource (lib "eagle-import") (part "C-EUC0805K"))
    )
    (comp (ref "C13")
      (value "100nF")
      (footprint "eagle-import:C0805K")
      (libsource (lib "eagle-import") (part "C-EUC0805K"))
    )
    (comp (ref "C17")
      (value "100nF")
      (footprint "eagle-import:C0805K")
      (libsource (lib "eagle-import") (part "C-EUC0805K"))
    )
    (comp (ref "C18")
      (value "100nF")
      (footprint "eagle-import:C0805K")
      (libsource (lib "eagle-import") (part "C-EUC0805K"))
    )
    (comp (ref "C20")
      (value "100nF")
      (footprint "eagle-import:C0805K")
      (libsource (lib "eagle-import") (part "C-EUC0805K"))
    )
    (comp (ref "C21")
      (value "100nF")
      (footprint "eagle-import:C0805K")
      (libsource (lib "eagle-import") (part "C-EUC0805K"))
    )
    (comp (ref "C35")
      (value "100nF")
      (footprint "eagle-import:C0805K")
      (libsource (lib "eagle-import") (part "C-EUC0805K"))
    )
    (comp (ref "C36")
      (value "1uF")
      (footprint "eagle-import:C0805K")
      (libsource (lib "eagle-import") (part "C-EUC0805K"))
    )
    (comp (ref "IC2")
      (value "4504D")
      (footprint "eagle-import:SO16")
      (libsource (lib "eagle-import") (part "4504D"))
    )
    (comp (ref "IC3")
      (value "4504D")
      (footprint "eagle-import:SO16")
      (libsource (lib "eagle-import") (part "4504D"))
    )
    (comp (ref "IC4")
      (value "4504D")
      (footprint "eagle-import:SO16")
      (libsource (lib "eagle-import") (part "4504D"))
    )
    (comp (ref "IC8")
      (value "OPA344N-SOT23")
      (footprint "eagle-import:SOT23-5")
      (libsource (lib "eagle-import") (part "OPA-SOT23344N"))
    )
    (comp (ref "JP39")
      (value "PINHD-1X1")
      (footprint "eagle-import:1X01")
      (libsource (lib "eagle-import") (part "PINHD-1X1"))
    )
    (comp (ref "JP40")
      (value "PINHD-1X1")
      (footprint "eagle-import:1X01")
      (libsource (lib "eagle-import") (part "PINHD-1X1"))
    )
    (comp (ref "R17")
      (value "1k")
      (footprint "eagle-import:R0805")
      (libsource (lib "eagle-import") (part "R-EU_R0805"))
    )
    (comp (ref "R18")
      (value "1k")
      (footprint "eagle-import:R0805")
      (libsource (lib "eagle-import") (part "R-EU_R0805"))
    )
    (comp (ref "R19")
      (value "0")
      (footprint "eagle-import:R0805")
      (libsource (lib "eagle-import") (part "R-EU_R0805"))
    )
    (comp (ref "R20")
      (value "1k")
      (footprint "eagle-import:R0805")
      (libsource (lib "eagle-import") (part "R-EU_R0805"))
    )
    (comp (ref "X3")
      (value "MSTBA2")
      (footprint "eagle-import:MSTBA2")
      (fields
        (field (name "MF") "FARNELL")
        (field (name "MPN") "1757242")
        (field (name "MF_1") "FARNELL")
        (field (name "MPN_1") "1757242")
        (field (name "OC_FARNELL") "3705171")
        (field (name "OC_NEWARK") "71C4161")
      )
      (libsource (lib "eagle-import") (part "MSTBA2"))
    )
    (comp (ref "X1")
      (value "F25HP")
      (footprint "eagle-import:F25HP")
      (libsource (lib "eagle-import") (part "F25HP"))
    )
    (comp (ref "C1")
      (value "12pF")
      (footprint "eagle-import:C0805K")
      (libsource (lib "eagle-import") (part "C-EUC0805K"))
    )
    (comp (ref "C2")
      (value "100nF")
      (footprint "eagle-import:C0805K")
      (libsource (lib "eagle-import") (part "C-EUC0805K"))
    )
    (comp (ref "C3")
      (value "1uF")
      (footprint "eagle-import:C0805K")
      (libsource (lib "eagle-import") (part "C-EUC0805K"))
    )
    (comp (ref "C4")
      (value "1uF")
      (footprint "eagle-import:C0805K")
      (libsource (lib "eagle-import") (part "C-EUC0805K"))
    )
    (comp (ref "C5")
      (value "100nF")
      (footprint "eagle-import:C0805K")
      (libsource (lib "eagle-import") (part "C-EUC0805K"))
    )
    (comp (ref "C6")
      (value "12pF")
      (footprint "eagle-import:C0805K")
      (libsource (lib "eagle-import") (part "C-EUC0805K"))
    )
    (comp (ref "C9")
      (value "1uF")
      (footprint "eagle-import:C0805K")
      (libsource (lib "eagle-import") (part "C-EUC0805K"))
    )
    (comp (ref "C10")
      (value "100nF")
      (footprint "eagle-import:C0805K")
      (libsource (lib "eagle-import") (part "C-EUC0805K"))
    )
    (comp (ref "C11")
      (value "12pF")
      (footprint "eagle-import:C0805K")
      (libsource (lib "eagle-import") (part "C-EUC0805K"))
    )
    (comp (ref "C14")
      (value "12pF")
      (footprint "eagle-import:C0805K")
      (libsource (lib "eagle-import") (part "C-EUC0805K"))
    )
    (comp (ref "C15")
      (value "100nF")
      (footprint "eagle-import:C0805K")
      (libsource (lib "eagle-import") (part "C-EUC0805K"))
    )
    (comp (ref "C16")
      (value "1uF")
      (footprint "eagle-import:C0805K")
      (libsource (lib "eagle-import") (part "C-EUC0805K"))
    )
    (comp (ref "C40")
      (value "10uF")
      (footprint "eagle-import:C0805K")
      (libsource (lib "eagle-import") (part "C-EUC0805K"))
    )
    (comp (ref "C41")
      (value "10uF")
      (footprint "eagle-import:C0805K")
      (libsource (lib "eagle-import") (part "C-EUC0805K"))
    )
    (comp (ref "IC1")
      (value "7805DT")
      (footprint "eagle-import:TO252")
      (libsource (lib "eagle-import") (part "78DT05"))
    )
    (comp (ref "IC5")
      (value "7810")
      (footprint "eagle-import:TO252")
      (libsource (lib "eagle-import") (part "78DT05"))
    )
    (comp (ref "IC9")
      (value "TR10")
      (footprint "eagle-import:TR10")
      (libsource (lib "eagle-import") (part "TR10"))
    )
    (comp (ref "JP1")
      (value "PINHD-1X8")
      (footprint "eagle-import:1X08")
      (libsource (lib "eagle-import") (part "PINHD-1X8"))
    )
    (comp (ref "JP2")
      (value "PINHD-1X2")
      (footprint "eagle-import:1X02")
      (libsource (lib "eagle-import") (part "PINHD-1X2"))
    )
    (comp (ref "JP20")
      (value "PINHD-1X2")
      (footprint "eagle-import:1X02")
      (libsource (lib "eagle-import") (part "PINHD-1X2"))
    )
    (comp (ref "JP21")
      (value "PINHD-1X2")
      (footprint "eagle-import:1X02")
      (libsource (lib "eagle-import") (part "PINHD-1X2"))
    )
    (comp (ref "L1")
      (value "L-USL1812")
      (footprint "eagle-import:L1812")
      (libsource (lib "eagle-import") (part "L-USL1812"))
    )
    (comp (ref "L2")
      (value "22uH")
      (footprint "eagle-import:DR127")
      (libsource (lib "eagle-import") (part "DR127"))
    )
    (comp (ref "Q7")
      (value "BSS84")
      (footprint "eagle-import:SOT23")
      (libsource (lib "eagle-import") (part "BSS84"))
    )
    (comp (ref "R23")
      (value "1M")
      (footprint "eagle-import:R0805")
      (libsource (lib "eagle-import") (part "R-EU_R0805"))
    )
    (comp (ref "X2")
      (value "MSTBA2")
      (footprint "eagle-import:MSTBA2")
      (fields (field (name "MF") "FARNELL") (field (name "MPN") "1757242"))
      (libsource (lib "eagle-import") (part "MSTBA2"))
    )
  )
  (nets
    (net (code "1") (name "+3V3") (class "Default")
      (node (ref "C12") (pin "1") (pinfunction "1_1") (pintype "passive"))
      (node (ref "C20") (pin "1") (pinfunction "1_1") (pintype "passive"))
      (node (ref "C21") (pin "1") (pinfunction "1_1") (pintype "passive"))
      (node (ref "C25") (pin "1") (pinfunction "1_1") (pintype "passive"))
      (node (ref "C28") (pin "2") (pinfunction "2_2") (pintype "passive"))
      (node (ref "C29") (pin "2") (pinfunction "2_2") (pintype "passive"))
      (node (ref "C30") (pin "2") (pinfunction "2_2") (pintype "passive"))
      (node (ref "C31") (pin "2") (pinfunction "2_2") (pintype "passive"))
      (node (ref "C32") (pin "2") (pinfunction "2_2") (pintype "passive"))
      (node (ref "IC2") (pin "1") (pinfunction "VCC_1") (pintype "power_in"))
      (node (ref "IC2") (pin "13") (pinfunction "MODE_13") (pintype "input"))
      (node (ref "IC3") (pin "1") (pinfunction "VCC_1") (pintype "power_in"))
      (node (ref "IC3") (pin "13") (pinfunction "MODE_13") (pintype "input"))
      (node (ref "IC4") (pin "1") (pinfunction "VCC_1") (pintype "power_in"))
      (node (ref "IC4") (pin "13") (pinfunction "MODE_13") (pintype "input"))
      (node (ref "IC7") (pin "20") (pinfunction "VCC_20") (pintype "power_in"))
      (node (ref "L4") (pin "1") (pinfunction "1_1") (pintype "passive"))
      (node (ref "R124") (pin "1") (pinfunction "1_1") (pintype "passive"))
      (node (ref "R16") (pin "2") (pinfunction "2_2") (pintype "passive"))
      (node (ref "R9") (pin "1") (pinfunction "1_1") (pintype "passive"))
      (node (ref "SV1") (pin "17") (pinfunction "17_17") (pintype "passive"))
      (node (ref "U2") (pin "15") (pinfunction "VDDTX_15") (pintype "power_in"))
      (node (ref "U2") (pin "19") (pinfunction "VDDRX_19") (pintype "power_in"))
      (node (ref "U2") (pin "20") (pinfunction "VDDPLL_20") (pintype "power_in"))
      (node (ref "U2") (pin "25") (pinfunction "VDDOSC_25") (pintype "power_in"))
      (node (ref "U2") (pin "28") (pinfunction "VDD_28") (pintype "power_in"))
    )
    (net (code "2") (name "+5V") (class "Default")
      (node (ref "C17") (pin "1") (pinfunction "1_1") (pintype "passive"))
      (node (ref "C18") (pin "1") (pinfunction "1_1") (pintype "passive"))
      (node (ref "C4") (pin "1") (pinfunction "1_1") (pintype "passive"))
      (node (ref "C5") (pin "1") (pinfunction "1_1") (pintype "passive"))
      (node (ref "C6") (pin "1") (pinfunction "1_1") (pintype "passive"))
      (node (ref "IC1") (pin "2") (pinfunction "VO_2") (pintype "passive"))
      (node (ref "IC2") (pin "16") (pinfunction "VDD_16") (pintype "power_in"))
      (node (ref "IC3") (pin "16") (pinfunction "VDD_16") (pintype "power_in"))
      (node (ref "IC9") (pin "P$3") (pinfunction "OUT_P$3") (pintype "bidirectional"))
      (node (ref "JP21") (pin "1") (pinfunction "1_1") (pintype "passive"))
      (node (ref "JP21") (pin "2") (pinfunction "2_2") (pintype "passive"))
      (node (ref "R12") (pin "2") (pinfunction "2_2") (pintype "passive"))
      (node (ref "R13") (pin "2") (pinfunction "2_2") (pintype "passive"))
      (node (ref "R14") (pin "1") (pinfunction "1_1") (pintype "passive"))
      (node (ref "R2") (pin "1") (pinfunction "1_1") (pintype "passive"))
      (node (ref "R3") (pin "1") (pinfunction "1_1") (pintype "passive"))
      (node (ref "R4") (pin "1") (pinfunction "1_1") (pintype "passive"))
      (node (ref "R5") (pin "1") (pinfunction "1_1") (pintype "passive"))
      (node (ref "SV2") (pin "19") (pinfunction "19_19") (pintype "passive"))
    )
    (net (code "3") (name "+5V_VBUS") (class "Default")
      (node (ref "SV1") (pin "19") (pinfunction "19_19") (pintype "passive"))
    )
    (net (code "4") (name "+10V") (class "Default")
      (node (ref "C1") (pin "1") (pinfunction "1_1") (pintype "passive"))
      (node (ref "C10") (pin "1") (pinfunction "1_1") (pintype "passive"))
      (node (ref "C11") (pin "1") (pinfunction "1_1") (pintype "passive"))
      (node (ref "C13") (pin "1") (pinfunction "1_1") (pintype "passive"))
      (node (ref "C2") (pin "1") (pinfunction "1_1") (pintype "passive"))
      (node (ref "C3") (pin "1") (pinfunction "1_1") (pintype "passive"))
      (node (ref "C35") (pin "1") (pinfunction "1_1") (pintype "passive"))
      (node (ref "C9") (pin "1") (pinfunction "1_1") (pintype "passive"))
      (node (ref "IC1") (pin "1") (pinfunction "VI_1") (pintype "input"))
      (node (ref "IC4") (pin "16") (pinfunction "VDD_16") (pintype "power_in"))
      (node (ref "IC5") (pin "2") (pinfunction "VO_2") (pintype "passive"))
      (node (ref "IC8") (pin "5") (pinfunction "V+_5") (pintype "power_in"))
      (node (ref "JP2") (pin "1") (pinfunction "1_1") (pintype "passive"))
      (node (ref "JP2") (pin "2") (pinfunction "2_2") (pintype "passive"))
    )
    (net (code "5") (name "+12V") (class "Default")
      (node (ref "C14") (pin "1") (pinfunction "1_1") (pintype "passive"))
      (node (ref "C15") (pin "1") (pinfunction "1_1") (pintype "passive"))
      (node (ref "C16") (pin "1") (pinfunction "1_1") (pintype "passive"))
      (node (ref "C37") (pin "1") (pinfunction "1_1") (pintype "passive"))
      (node (ref "C38") (pin "1") (pinfunction "1_1") (pintype "passive"))
      (node (ref "C39") (pin "1") (pinfunction "1_1") (pintype "passive"))
      (node (ref "C41") (pin "1") (pinfunction "1_1") (pintype "passive"))
      (node (ref "C8") (pin "1") (pinfunction "1_1") (pintype "passive"))
      (node (ref "D1") (pin "C") (pinfunction "C_C") (pintype "passive"))
      (node (ref "D2") (pin "C") (pinfunction "C_C") (pintype "passive"))
      (node (ref "IC5") (pin "1") (pinfunction "VI_1") (pintype "input"))
      (node (ref "IC6") (pin "2") (pinfunction "+VIN_2") (pintype "bidirectional"))
      (node (ref "JP20") (pin "1") (pinfunction "1_1") (pintype "passive"))
      (node (ref "JP20") (pin "2") (pinfunction "2_2") (pintype "passive"))
      (node (ref "K1") (pin "1") (pinfunction "1_1") (pintype "passive"))
      (node (ref "K2") (pin "1") (pinfunction "1_1") (pintype "passive"))
      (node (ref "L2") (pin "1") (pinfunction "1_1") (pintype "passive"))
      (node (ref "Q7") (pin "2") (pinfunction "S_2") (pintype "passive"))
      (node (ref "R15") (pin "2") (pinfunction "2_2") (pintype "passive"))
    )
    (net (code "6") (name "ABORT") (class "Default")
      (node (ref "IC7") (pin "11") (pinfunction "A1_11") (pintype "input"))
      (node (ref "R5") (pin "2") (pinfunction "2_2") (pintype "passive"))
      (node (ref "X1") (pin "10") (pinfunction "10_10") (pintype "passive"))
    )
    (net (code "7") (name "AGND") (class "Default")
      (node (ref "SV2") (pin "17") (pinfunction "17_17") (pintype "passive"))
    )
    (net (code "8") (name "AREF") (class "Default")
      (node (ref "SV2") (pin "18") (pinfunction "18_18") (pintype "passive"))
    )
    (net (code "9") (name "DIRECTION_A") (class "Default")
      (node (ref "IC3") (pin "6") (pinfunction "CO_6") (pintype "output"))
      (node (ref "X1") (pin "9") (pinfunction "9_9") (pintype "passive"))
    )
    (net (code "10") (name "DIRECTION_X") (class "Default")
      (node (ref "IC2") (pin "4") (pinfunction "BO_4") (pintype "output"))
      (node (ref "X1") (pin "3") (pinfunction "3_3") (pintype "passive"))
    )
    (net (code "11") (name "DIRECTION_Y") (class "Default")
      (node (ref "IC2") (pin "10") (pinfunction "DO_10") (pintype "output"))
      (node (ref "X1") (pin "5") (pinfunction "5_5") (pintype "passive"))
    )
    (net (code "12") (name "DIRECTION_Z") (class "Default")
      (node (ref "IC2") (pin "15") (pinfunction "FO_15") (pintype "output"))
      (node (ref "X1") (pin "7") (pinfunction "7_7") (pintype "passive"))
    )
    (net (code "13") (name "ENC_INT") (class "Default")
      (node (ref "U2") (pin "4") (pinfunction "INT_4") (pintype "output"))
    )
    (net (code "14") (name "ETH_RST") (class "Default")
      (node (ref "R9") (pin "2") (pinfunction "2_2") (pintype "passive"))
      (node (ref "SJ3") (pin "1") (pinfunction "1_1") (pintype "passive"))
      (node (ref "U2") (pin "10") (pinfunction "RESET_10") (pintype "input"))
    )
    (net (code "15") (name "ETH_WOL") (class "Default")
      (node (ref "U2") (pin "5") (pinfunction "WOL_5") (pintype "output"))
    )
    (net (code "16") (name "EXTERNAL_POWER") (class "Default")
      (node (ref "OK4") (pin "12") (pinfunction "COL_12") (pintype "passive"))
      (node (ref "R16") (pin "1") (pinfunction "1_1") (pintype "passive"))
      (node (ref "SJ2") (pin "1") (pinfunction "1_1") (pintype "passive"))
    )
    (net (code "17") (name "GND") (class "Default")
      (node (ref "C1") (pin "2") (pinfunction "2_2") (pintype "passive"))
      (node (ref "C10") (pin "2") (pinfunction "2_2") (pintype "passive"))
      (node (ref "C11") (pin "2") (pinfunction "2_2") (pintype "passive"))
      (node (ref "C12") (pin "2") (pinfunction "2_2") (pintype "passive"))
      (node (ref "C13") (pin "2") (pinfunction "2_2") (pintype "passive"))
      (node (ref "C14") (pin "2") (pinfunction "2_2") (pintype "passive"))
      (node (ref "C15") (pin "2") (pinfunction "2_2") (pintype "passive"))
      (node (ref "C16") (pin "2") (pinfunction "2_2") (pintype "passive"))
      (node (ref "C17") (pin "2") (pinfunction "2_2") (pintype "passive"))
      (node (ref "C18") (pin "2") (pinfunction "2_2") (pintype "passive"))
      (node (ref "C2") (pin "2") (pinfunction "2_2") (pintype "passive"))
      (node (ref "C20") (pin "2") (pinfunction "2_2") (pintype "passive"))
      (node (ref "C21") (pin "2") (pinfunction "2_2") (pintype "passive"))
      (node (ref "C24") (pin "2") (pinfunction "2_2") (pintype "passive"))
      (node (ref "C25") (pin "2") (pinfunction "2_2") (pintype "passive"))
      (node (ref "C26") (pin "2") (pinfunction "2_2") (pintype "passive"))
      (node (ref "C27") (pin "1") (pinfunction "1_1") (pintype "passive"))
      (node (ref "C28") (pin "1") (pinfunction "1_1") (pintype "passive"))
      (node (ref "C29") (pin "1") (pinfunction "1_1") (pintype "passive"))
      (node (ref "C3") (pin "2") (pinfunction "2_2") (pintype "passive"))
      (node (ref "C30") (pin "1") (pinfunction "1_1") (pintype "passive"))
      (node (ref "C31") (pin "1") (pinfunction "1_1") (pintype "passive"))
      (node (ref "C32") (pin "1") (pinfunction "1_1") (pintype "passive"))
      (node (ref "C33") (pin "2") (pinfunction "2_2") (pintype "passive"))
      (node (ref "C34") (pin "1") (pinfunction "1_1") (pintype "passive"))
      (node (ref "C35") (pin "2") (pinfunction "2_2") (pintype "passive"))
      (node (ref "C37") (pin "2") (pinfunction "2_2") (pintype "passive"))
      (node (ref "C38") (pin "2") (pinfunction "2_2") (pintype "passive"))
      (node (ref "C39") (pin "2") (pinfunction "2_2") (pintype "passive"))
      (node (ref "C4") (pin "2") (pinfunction "2_2") (pintype "passive"))
      (node (ref "C40") (pin "2") (pinfunction "2_2") (pintype "passive"))
      (node (ref "C41") (pin "2") (pinfunction "2_2") (pintype "passive"))
      (node (ref "C5") (pin "2") (pinfunction "2_2") (pintype "passive"))
      (node (ref "C6") (pin "2") (pinfunction "2_2") (pintype "passive"))
      (node (ref "C7") (pin "2") (pinfunction "2_2") (pintype "passive"))
      (node (ref "C8") (pin "2") (pinfunction "2_2") (pintype "passive"))
      (node (ref "C9") (pin "2") (pinfunction "2_2") (pintype "passive"))
      (node (ref "IC1") (pin "3") (pinfunction "GND_3") (pintype "passive"))
      (node (ref "IC2") (pin "8") (pinfunction "GND_8") (pintype "power_in"))
      (node (ref "IC3") (pin "14") (pinfunction "FI_14") (pintype "input"))
      (node (ref "IC3") (pin "8") (pinfunction "GND_8") (pintype "power_in"))
      (node (ref "IC4") (pin "11") (pinfunction "EI_11") (pintype "input"))
      (node (ref "IC4") (pin "14") (pinfunction "FI_14") (pintype "input"))
      (node (ref "IC4") (pin "5") (pinfunction "BI_5") (pintype "input"))
      (node (ref "IC4") (pin "7") (pinfunction "CI_7") (pintype "input"))
      (node (ref "IC4") (pin "8") (pinfunction "GND_8") (pintype "power_in"))
      (node (ref "IC4") (pin "9") (pinfunction "DI_9") (pintype "input"))
      (node (ref "IC5") (pin "3") (pinfunction "GND_3") (pintype "passive"))
      (node (ref "IC6") (pin "1") (pinfunction "-VIN_1") (pintype "bidirectional"))
      (node (ref "IC7") (pin "1") (pinfunction "G_1") (pintype "input"))
      (node (ref "IC7") (pin "10") (pinfunction "GND_10") (pintype "power_in"))
      (node (ref "IC7") (pin "17") (pinfunction "A4_17") (pintype "input"))
      (node (ref "IC7") (pin "19") (pinfunction "G_19") (pintype "input"))
      (node (ref "IC8") (pin "2") (pinfunction "V-_2") (pintype "power_in"))
      (node (ref "IC9") (pin "P$2") (pinfunction "GND_P$2") (pintype "bidirectional"))
      (node (ref "JP1") (pin "1") (pinfunction "1_1") (pintype "passive"))
      (node (ref "JP1") (pin "2") (pinfunction "2_2") (pintype "passive"))
      (node (ref "JP1") (pin "3") (pinfunction "3_3") (pintype "passive"))
      (node (ref "JP1") (pin "4") (pinfunction "4_4") (pintype "passive"))
      (node (ref "JP1") (pin "5") (pinfunction "5_5") (pintype "passive"))
      (node (ref "JP1") (pin "6") (pinfunction "6_6") (pintype "passive"))
      (node (ref "JP1") (pin "7") (pinfunction "7_7") (pintype "passive"))
      (node (ref "JP1") (pin "8") (pinfunction "8_8") (pintype "passive"))
      (node (ref "JP40") (pin "1") (pinfunction "1_1") (pintype "passive"))
      (node (ref "OK4") (pin "11") (pinfunction "EMIT_11") (pintype "passive"))
      (node (ref "OK4") (pin "13") (pinfunction "EMIT_13") (pintype "passive"))
      (node (ref "OK4") (pin "15") (pinfunction "EMIT_15") (pintype "passive"))
      (node (ref "OK4") (pin "6") (pinfunction "C_6") (pintype "passive"))
      (node (ref "Q4") (pin "E") (pinfunction "E_E") (pintype "passive"))
      (node (ref "Q5") (pin "E") (pinfunction "E_E") (pintype "passive"))
      (node (ref "R20") (pin "2") (pinfunction "2_2") (pintype "passive"))
      (node (ref "R21") (pin "1") (pinfunction "1_1") (pintype "passive"))
      (node (ref "R22") (pin "1") (pinfunction "1_1") (pintype "passive"))
      (node (ref "R23") (pin "1") (pinfunction "1_1") (pintype "passive"))
      (node (ref "R7") (pin "2") (pinfunction "2_2") (pintype "passive"))
      (node (ref "SV1") (pin "18") (pinfunction "18_18") (pintype "passive"))
      (node (ref "SV1") (pin "20") (pinfunction "20_20") (pintype "passive"))
      (node (ref "SV2") (pin "20") (pinfunction "20_20") (pintype "passive"))
      (node (ref "U$15") (pin "10") (pinfunction "A-L_10") (pintype "passive"))
      (node (ref "U$15") (pin "12") (pinfunction "A-R_12") (pintype "passive"))
      (node (ref "U$15") (pin "8") (pinfunction "8_8") (pintype "input"))
      (node (ref "U2") (pin "11") (pinfunction "VSSRX_11") (pintype "power_in"))
      (node (ref "U2") (pin "18") (pinfunction "VSSTX_18") (pintype "power_in"))
      (node (ref "U2") (pin "2") (pinfunction "VSS_2") (pintype "power_in"))
      (node (ref "U2") (pin "21") (pinfunction "VSSPLL_21") (pintype "power_in"))
      (node (ref "U2") (pin "22") (pinfunction "VSSOSC_22") (pintype "power_in"))
      (node (ref "UEXT") (pin "2") (pinfunction "2_2") (pintype "passive"))
      (node (ref "X1") (pin "18") (pinfunction "18_18") (pintype "passive"))
      (node (ref "X1") (pin "19") (pinfunction "19_19") (pintype "passive"))
      (node (ref "X1") (pin "20") (pinfunction "20_20") (pintype "passive"))
      (node (ref "X1") (pin "21") (pinfunction "21_21") (pintype "passive"))
      (node (ref "X1") (pin "22") (pinfunction "22_22") (pintype "passive"))
      (node (ref "X1") (pin "23") (pinfunction "23_23") (pintype "passive"))
      (node (ref "X1") (pin "24") (pinfunction "24_24") (pintype "passive"))
      (node (ref "X1") (pin "25") (pinfunction "25_25") (pintype "passive"))
      (node (ref "X1") (pin "G1") (pinfunction "G1_G1") (pintype "passive"))
      (node (ref "X1") (pin "G2") (pinfunction "G2_G2") (pintype "passive"))
      (node (ref "X2") (pin "2") (pinfunction "1_2") (pintype "passive"))
      (node (ref "X3") (pin "2") (pinfunction "1_2") (pintype "passive"))
    )
    (net (code "18") (name "LIMIT_A") (class "Default")
      (node (ref "X1") (pin "16") (pinfunction "16_16") (pintype "passive"))
    )
    (net (code "19") (name "LIMIT_X") (class "Default")
      (node (ref "IC7") (pin "2") (pinfunction "A1_2") (pintype "input"))
      (node (ref "R14") (pin "2") (pinfunction "2_2") (pintype "passive"))
      (node (ref "X1") (pin "11") (pinfunction "11_11") (pintype "passive"))
    )
    (net (code "20") (name "LIMIT_Y") (class "Default")
      (node (ref "IC7") (pin "6") (pinfunction "A3_6") (pintype "input"))
      (node (ref "R3") (pin "2") (pinfunction "2_2") (pintype "passive"))
      (node (ref "X1") (pin "13") (pinfunction "13_13") (pintype "passive"))
    )
    (net (code "21") (name "LIMIT_Z") (class "Default")
      (node (ref "IC7") (pin "4") (pinfunction "A2_4") (pintype "input"))
      (node (ref "R2") (pin "2") (pinfunction "2_2") (pintype "passive"))
      (node (ref "X1") (pin "12") (pinfunction "12_12") (pintype "passive"))
    )
    (net (code "22") (name "MISO") (class "Default")
      (node (ref "U2") (pin "6") (pinfunction "SO_6") (pintype "output"))
      (node (ref "UEXT") (pin "7") (pinfunction "7_7") (pintype "passive"))
    )
    (net (code "23") (name "MIST_AIR") (class "Default")
      (node (ref "R25") (pin "1") (pinfunction "1_1") (pintype "passive"))
      (node (ref "SJ4") (pin "1") (pinfunction "1_1") (pintype "passive"))
    )
    (net (code "24") (name "MIST_OIL") (class "Default")
      (node (ref "R24") (pin "1") (pinfunction "1_1") (pintype "passive"))
      (node (ref "SJ5") (pin "1") (pinfunction "1_1") (pintype "passive"))
    )
    (net (code "25") (name "MOSI") (class "Default")
      (node (ref "U2") (pin "7") (pinfunction "SI_7") (pintype "input"))
      (node (ref "UEXT") (pin "8") (pinfunction "8_8") (pintype "passive"))
    )
    (net (code "26") (name "Net-(C33-Pad1)") (class "Default")
      (node (ref "C33") (pin "1") (pinfunction "1_1") (pintype "passive"))
      (node (ref "R79") (pin "2") (pinfunction "2_2") (pintype "passive"))
      (node (ref "R80") (pin "1") (pinfunction "1_1") (pintype "passive"))
      (node (ref "SJ1") (pin "1") (pinfunction "1_1") (pintype "passive"))
    )
    (net (code "27") (name "Net-(C36-Pad1)") (class "Default")
      (node (ref "C36") (pin "1") (pinfunction "1_1") (pintype "passive"))
      (node (ref "R17") (pin "2") (pinfunction "2_2") (pintype "passive"))
      (node (ref "R18") (pin "1") (pinfunction "1_1") (pintype "passive"))
    )
    (net (code "28") (name "Net-(D1-PadA)") (class "Default")
      (node (ref "D1") (pin "A") (pinfunction "A_A") (pintype "passive"))
      (node (ref "K2") (pin "2") (pinfunction "2_2") (pintype "passive"))
      (node (ref "Q4") (pin "C") (pinfunction "C_C") (pintype "passive"))
    )
    (net (code "29") (name "Net-(D2-PadA)") (class "Default")
      (node (ref "D2") (pin "A") (pinfunction "A_A") (pintype "passive"))
      (node (ref "K1") (pin "2") (pinfunction "2_2") (pintype "passive"))
      (node (ref "Q5") (pin "C") (pinfunction "C_C") (pintype "passive"))
    )
    (net (code "30") (name "Net-(IC6-+VOUT)") (class "Default")
      (node (ref "C19") (pin "1") (pinfunction "1_1") (pintype "passive"))
      (node (ref "C22") (pin "1") (pinfunction "1_1") (pintype "passive"))
      (node (ref "C23") (pin "1") (pinfunction "1_1") (pintype "passive"))
      (node (ref "IC6") (pin "4") (pinfunction "+VOUT_4") (pintype "bidirectional"))
      (node (ref "R1") (pin "1") (pinfunction "1_1") (pintype "passive"))
      (node (ref "R6") (pin "2") (pinfunction "2_2") (pintype "passive"))
      (node (ref "R8") (pin "1") (pinfunction "1_1") (pintype "passive"))
    )
    (net (code "31") (name "Net-(IC6--VOUT)") (class "Default")
      (node (ref "C19") (pin "2") (pinfunction "2_2") (pintype "passive"))
      (node (ref "C22") (pin "2") (pinfunction "2_2") (pintype "passive"))
      (node (ref "C23") (pin "2") (pinfunction "2_2") (pintype "passive"))
      (node (ref "IC6") (pin "3") (pinfunction "-VOUT_3") (pintype "bidirectional"))
      (node (ref "R6") (pin "1") (pinfunction "1_1") (pintype "passive"))
      (node (ref "X4") (pin "2") (pinfunction "1_2") (pintype "passive"))
      (node (ref "X5") (pin "2") (pinfunction "1_2") (pintype "passive"))
    )
    (net (code "32") (name "Net-(IC8-+IN)") (class "Default")
      (node (ref "C7") (pin "1") (pinfunction "1_1") (pintype "passive"))
      (node (ref "IC8") (pin "3") (pinfunction "+IN_3") (pintype "input"))
      (node (ref "R17") (pin "1") (pinfunction "1_1") (pintype "passive"))
    )
    (net (code "33") (name "Net-(IC8--IN)") (class "Default")
      (node (ref "IC8") (pin "4") (pinfunction "-IN_4") (pintype "input"))
      (node (ref "R19") (pin "2") (pinfunction "2_2") (pintype "passive"))
      (node (ref "R20") (pin "1") (pinfunction "1_1") (pintype "passive"))
    )
    (net (code "34") (name "Net-(IC9-IN)") (class "Default")
      (node (ref "C40") (pin "1") (pinfunction "1_1") (pintype "passive"))
      (node (ref "IC9") (pin "P$1") (pinfunction "IN_P$1") (pintype "bidirectional"))
      (node (ref "L2") (pin "2") (pinfunction "2_2") (pintype "passive"))
    )
    (net (code "35") (name "Net-(K1B-O)") (class "Default")
      (node (ref "K1") (pin "O1") (pinfunction "O_O1") (pintype "passive"))
      (node (ref "K1") (pin "O2") (pinfunction "O_O2") (pintype "passive"))
    )
    (net (code "36") (name "Net-(K1B-P)") (class "Default")
      (node (ref "K1") (pin "P1") (pinfunction "P_P1") (pintype "passive"))
      (node (ref "K1") (pin "P2") (pinfunction "P_P2") (pintype "passive"))
      (node (ref "X6") (pin "2") (pinfunction "1_2") (pintype "passive"))
    )
    (net (code "37") (name "Net-(K1B-S)") (class "Default")
      (node (ref "K1") (pin "S1") (pinfunction "S_S1") (pintype "passive"))
      (node (ref "K1") (pin "S2") (pinfunction "S_S2") (pintype "passive"))
      (node (ref "X6") (pin "1") (pinfunction "1_1") (pintype "passive"))
    )
    (net (code "38") (name "Net-(K2B-O)") (class "Default")
      (node (ref "K2") (pin "O1") (pinfunction "O_O1") (pintype "passive"))
      (node (ref "K2") (pin "O2") (pinfunction "O_O2") (pintype "passive"))
    )
    (net (code "39") (name "Net-(K2B-P)") (class "Default")
      (node (ref "K2") (pin "P1") (pinfunction "P_P1") (pintype "passive"))
      (node (ref "K2") (pin "P2") (pinfunction "P_P2") (pintype "passive"))
      (node (ref "X7") (pin "2") (pinfunction "1_2") (pintype "passive"))
    )
    (net (code "40") (name "Net-(K2B-S)") (class "Default")
      (node (ref "K2") (pin "S1") (pinfunction "S_S1") (pintype "passive"))
      (node (ref "K2") (pin "S2") (pinfunction "S_S2") (pintype "passive"))
      (node (ref "X7") (pin "1") (pinfunction "1_1") (pintype "passive"))
    )
    (net (code "41") (name "Net-(L1-Pad1)") (class "Default")
      (node (ref "L1") (pin "1") (pinfunction "1_1") (pintype "passive"))
      (node (ref "X2") (pin "1") (pinfunction "1_1") (pintype "passive"))
    )
    (net (code "42") (name "Net-(OK4A-A)") (class "Default")
      (node (ref "OK4") (pin "1") (pinfunction "A_1") (pintype "passive"))
      (node (ref "R1") (pin "2") (pinfunction "2_2") (pintype "passive"))
    )
    (net (code "43") (name "Net-(OK4A-C)") (class "Default")
      (node (ref "OK4") (pin "2") (pinfunction "C_2") (pintype "passive"))
      (node (ref "X4") (pin "1") (pinfunction "1_1") (pintype "passive"))
    )
    (net (code "44") (name "Net-(OK4B-A)") (class "Default")
      (node (ref "OK4") (pin "3") (pinfunction "A_3") (pintype "passive"))
      (node (ref "R8") (pin "2") (pinfunction "2_2") (pintype "passive"))
    )
    (net (code "45") (name "Net-(OK4B-C)") (class "Default")
      (node (ref "JP3") (pin "1") (pinfunction "1_1") (pintype "passive"))
      (node (ref "OK4") (pin "4") (pinfunction "C_4") (pintype "passive"))
      (node (ref "X5") (pin "1") (pinfunction "1_1") (pintype "passive"))
    )
    (net (code "46") (name "Net-(OK4C-A)") (class "Default")
      (node (ref "OK4") (pin "5") (pinfunction "A_5") (pintype "passive"))
      (node (ref "R15") (pin "1") (pinfunction "1_1") (pintype "passive"))
    )
    (net (code "47") (name "Net-(Q2-2)") (class "Default")
      (node (ref "C24") (pin "1") (pinfunction "1_1") (pintype "passive"))
      (node (ref "Q2") (pin "3") (pinfunction "2_3") (pintype "passive"))
      (node (ref "U2") (pin "24") (pinfunction "OSC2_24") (pintype "output"))
    )
    (net (code "48") (name "Net-(Q4-PadB)") (class "Default")
      (node (ref "Q4") (pin "B") (pinfunction "B_B") (pintype "passive"))
      (node (ref "R22") (pin "2") (pinfunction "2_2") (pintype "passive"))
      (node (ref "R24") (pin "2") (pinfunction "2_2") (pintype "passive"))
    )
    (net (code "49") (name "Net-(Q5-PadB)") (class "Default")
      (node (ref "Q5") (pin "B") (pinfunction "B_B") (pintype "passive"))
      (node (ref "R21") (pin "2") (pinfunction "2_2") (pintype "passive"))
      (node (ref "R25") (pin "2") (pinfunction "2_2") (pintype "passive"))
    )
    (net (code "50") (name "Net-(Q7-D)") (class "Default")
      (node (ref "L1") (pin "2") (pinfunction "2_2") (pintype "passive"))
      (node (ref "Q7") (pin "3") (pinfunction "D_3") (pintype "passive"))
    )
    (net (code "51") (name "Net-(Q7-G)") (class "Default")
      (node (ref "Q7") (pin "1") (pinfunction "G_1") (pintype "passive"))
      (node (ref "R23") (pin "2") (pinfunction "2_2") (pintype "passive"))
    )
    (net (code "52") (name "Net-(U$15-C-L)") (class "Default")
      (node (ref "R11") (pin "1") (pinfunction "1_1") (pintype "passive"))
      (node (ref "U$15") (pin "9") (pinfunction "C-L_9") (pintype "passive"))
    )
    (net (code "53") (name "Net-(U$15-C-R)") (class "Default")
      (node (ref "R10") (pin "1") (pinfunction "1_1") (pintype "passive"))
      (node (ref "U$15") (pin "11") (pinfunction "C-R_11") (pintype "passive"))
    )
    (net (code "54") (name "Net-(U$15-CR)") (class "Default")
      (node (ref "SJ1") (pin "2") (pinfunction "2_2") (pintype "passive"))
      (node (ref "U$15") (pin "5") (pinfunction "CR_5") (pintype "input"))
    )
    (net (code "55") (name "Net-(U$15-CT)") (class "Default")
      (node (ref "C34") (pin "2") (pinfunction "2_2") (pintype "passive"))
      (node (ref "L4") (pin "2") (pinfunction "2_2") (pintype "passive"))
      (node (ref "R81") (pin "2") (pinfunction "2_2") (pintype "passive"))
      (node (ref "R82") (pin "1") (pinfunction "1_1") (pintype "passive"))
      (node (ref "U$15") (pin "2") (pinfunction "CT_2") (pintype "input"))
    )
    (net (code "56") (name "Net-(U$15-RD+)") (class "Default")
      (node (ref "R80") (pin "2") (pinfunction "2_2") (pintype "passive"))
      (node (ref "U$15") (pin "4") (pinfunction "RD+_4") (pintype "input"))
      (node (ref "U2") (pin "13") (pinfunction "TPIN+_13") (pintype "input"))
    )
    (net (code "57") (name "Net-(U$15-RD-)") (class "Default")
      (node (ref "R79") (pin "1") (pinfunction "1_1") (pintype "passive"))
      (node (ref "U$15") (pin "6") (pinfunction "RD-_6") (pintype "input"))
      (node (ref "U2") (pin "12") (pinfunction "TPIN-_12") (pintype "input"))
    )
    (net (code "58") (name "Net-(U$15-TD+)") (class "Default")
      (node (ref "R82") (pin "2") (pinfunction "2_2") (pintype "passive"))
      (node (ref "U$15") (pin "1") (pinfunction "TD+_1") (pintype "input"))
      (node (ref "U2") (pin "17") (pinfunction "TPOUT+_17") (pintype "output"))
    )
    (net (code "59") (name "Net-(U$15-TD-)") (class "Default")
      (node (ref "R81") (pin "1") (pinfunction "1_1") (pintype "passive"))
      (node (ref "U$15") (pin "3") (pinfunction "TD-_3") (pintype "input"))
      (node (ref "U2") (pin "16") (pinfunction "TPOUT-_16") (pintype "output"))
    )
    (net (code "60") (name "Net-(U2-LEDA)") (class "Default")
      (node (ref "R10") (pin "2") (pinfunction "2_2") (pintype "passive"))
      (node (ref "U2") (pin "27") (pinfunction "LEDA_27") (pintype "output"))
    )
    (net (code "61") (name "Net-(U2-LEDB)") (class "Default")
      (node (ref "R11") (pin "2") (pinfunction "2_2") (pintype "passive"))
      (node (ref "U2") (pin "26") (pinfunction "LEDB_26") (pintype "output"))
    )
    (net (code "62") (name "Net-(U2-OSC1)") (class "Default")
      (node (ref "C26") (pin "1") (pinfunction "1_1") (pintype "passive"))
      (node (ref "Q2") (pin "1") (pinfunction "1_1") (pintype "passive"))
      (node (ref "U2") (pin "23") (pinfunction "OSC1_23") (pintype "input"))
    )
    (net (code "63") (name "Net-(U2-RBIAS)") (class "Default")
      (node (ref "R7") (pin "1") (pinfunction "1_1") (pintype "passive"))
      (node (ref "U2") (pin "14") (pinfunction "RBIAS_14") (pintype "passive"))
    )
    (net (code "64") (name "Net-(U2-VCAP)") (class "Default")
      (node (ref "C27") (pin "2") (pinfunction "2_2") (pintype "passive"))
      (node (ref "U2") (pin "1") (pinfunction "VCAP_1") (pintype "power_in"))
    )
    (net (code "65") (name "PROBE") (class "Default")
      (node (ref "IC7") (pin "8") (pinfunction "A4_8") (pintype "input"))
      (node (ref "R4") (pin "2") (pinfunction "2_2") (pintype "passive"))
      (node (ref "X1") (pin "15") (pinfunction "15_15") (pintype "passive"))
    )
    (net (code "66") (name "PROBE_ISOLATED") (class "Default")
      (node (ref "IC7") (pin "13") (pinfunction "A2_13") (pintype "input"))
      (node (ref "OK4") (pin "16") (pinfunction "COL_16") (pintype "passive"))
      (node (ref "R12") (pin "1") (pinfunction "1_1") (pintype "passive"))
    )
    (net (code "67") (name "RB0") (class "Default")
      (node (ref "IC7") (pin "16") (pinfunction "Y2_16") (pintype "tri_state"))
      (node (ref "SV2") (pin "16") (pinfunction "16_16") (pintype "passive"))
    )
    (net (code "68") (name "RB1") (class "Default")
      (node (ref "SV1") (pin "16") (pinfunction "16_16") (pintype "passive"))
    )
    (net (code "69") (name "RB2") (class "Default")
      (node (ref "SV1") (pin "15") (pinfunction "15_15") (pintype "passive"))
    )
    (net (code "70") (name "RB3") (class "Default")
      (node (ref "SV1") (pin "14") (pinfunction "14_14") (pintype "passive"))
    )
    (net (code "71") (name "RB4") (class "Default")
      (node (ref "SV1") (pin "13") (pinfunction "13_13") (pintype "passive"))
    )
    (net (code "72") (name "RB8") (class "Default")
      (node (ref "SV1") (pin "12") (pinfunction "12_12") (pintype "passive"))
    )
    (net (code "73") (name "RB9") (class "Default")
      (node (ref "SV1") (pin "11") (pinfunction "11_11") (pintype "passive"))
    )
    (net (code "74") (name "RB10") (class "Default")
      (node (ref "SV1") (pin "10") (pinfunction "10_10") (pintype "passive"))
    )
    (net (code "75") (name "RB11") (class "Default")
      (node (ref "SV1") (pin "9") (pinfunction "9_9") (pintype "passive"))
    )
    (net (code "76") (name "RB12") (class "Default")
      (node (ref "SJ5") (pin "2") (pinfunction "2_2") (pintype "passive"))
      (node (ref "SV1") (pin "8") (pinfunction "8_8") (pintype "passive"))
    )
    (net (code "77") (name "RB14") (class "Default")
      (node (ref "SJ4") (pin "2") (pinfunction "2_2") (pintype "passive"))
      (node (ref "SV1") (pin "7") (pinfunction "7_7") (pintype "passive"))
    )
    (net (code "78") (name "RC13") (class "Default")
      (node (ref "IC7") (pin "7") (pinfunction "Y2_7") (pintype "tri_state"))
      (node (ref "SV2") (pin "2") (pinfunction "2_2") (pintype "passive"))
    )
    (net (code "79") (name "RC14") (class "Default")
      (node (ref "IC7") (pin "5") (pinfunction "Y3_5") (pintype "tri_state"))
      (node (ref "SV2") (pin "1") (pinfunction "1_1") (pintype "passive"))
    )
    (net (code "80") (name "RD1") (class "Default")
      (node (ref "IC3") (pin "11") (pinfunction "EI_11") (pintype "input"))
      (node (ref "IC4") (pin "3") (pinfunction "AI_3") (pintype "input"))
      (node (ref "SV1") (pin "6") (pinfunction "6_6") (pintype "passive"))
    )
    (net (code "81") (name "RD1_10V") (class "Default")
      (node (ref "IC4") (pin "2") (pinfunction "AO_2") (pintype "output"))
      (node (ref "R18") (pin "2") (pinfunction "2_2") (pintype "passive"))
    )
    (net (code "82") (name "RD2") (class "Default")
      (node (ref "SV1") (pin "5") (pinfunction "5_5") (pintype "passive"))
    )
    (net (code "83") (name "RD3") (class "Default")
      (node (ref "SJ3") (pin "2") (pinfunction "2_2") (pintype "passive"))
      (node (ref "SV1") (pin "4") (pinfunction "4_4") (pintype "passive"))
    )
    (net (code "84") (name "RD4") (class "Default")
      (node (ref "IC3") (pin "9") (pinfunction "DI_9") (pintype "input"))
      (node (ref "SV1") (pin "3") (pinfunction "3_3") (pintype "passive"))
    )
    (net (code "85") (name "RD5") (class "Default")
      (node (ref "SV1") (pin "2") (pinfunction "2_2") (pintype "passive"))
    )
    (net (code "86") (name "RD6") (class "Default")
      (node (ref "SJ2") (pin "2") (pinfunction "2_2") (pintype "passive"))
      (node (ref "SV1") (pin "1") (pinfunction "1_1") (pintype "passive"))
    )
    (net (code "87") (name "RD7") (class "Default")
      (node (ref "IC7") (pin "9") (pinfunction "Y1_9") (pintype "tri_state"))
      (node (ref "SV2") (pin "15") (pinfunction "15_15") (pintype "passive"))
    )
    (net (code "88") (name "RD8") (class "Default")
      (node (ref "IC7") (pin "12") (pinfunction "Y4_12") (pintype "tri_state"))
      (node (ref "SV2") (pin "14") (pinfunction "14_14") (pintype "passive"))
    )
    (net (code "89") (name "RD11") (class "Default")
      (node (ref "IC7") (pin "18") (pinfunction "Y1_18") (pintype "tri_state"))
      (node (ref "SV2") (pin "13") (pinfunction "13_13") (pintype "passive"))
    )
    (net (code "90") (name "RE0") (class "Default")
      (node (ref "IC2") (pin "3") (pinfunction "AI_3") (pintype "input"))
      (node (ref "SV2") (pin "3") (pinfunction "3_3") (pintype "passive"))
    )
    (net (code "91") (name "RE1") (class "Default")
      (node (ref "IC2") (pin "5") (pinfunction "BI_5") (pintype "input"))
      (node (ref "SV2") (pin "4") (pinfunction "4_4") (pintype "passive"))
    )
    (net (code "92") (name "RE2") (class "Default")
      (node (ref "IC2") (pin "7") (pinfunction "CI_7") (pintype "input"))
      (node (ref "SV2") (pin "5") (pinfunction "5_5") (pintype "passive"))
    )
    (net (code "93") (name "RE3") (class "Default")
      (node (ref "IC2") (pin "9") (pinfunction "DI_9") (pintype "input"))
      (node (ref "SV2") (pin "6") (pinfunction "6_6") (pintype "passive"))
    )
    (net (code "94") (name "RE4") (class "Default")
      (node (ref "IC2") (pin "11") (pinfunction "EI_11") (pintype "input"))
      (node (ref "SV2") (pin "7") (pinfunction "7_7") (pintype "passive"))
    )
    (net (code "95") (name "RE5") (class "Default")
      (node (ref "IC2") (pin "14") (pinfunction "FI_14") (pintype "input"))
      (node (ref "SV2") (pin "8") (pinfunction "8_8") (pintype "passive"))
    )
    (net (code "96") (name "RE6") (class "Default")
      (node (ref "IC3") (pin "3") (pinfunction "AI_3") (pintype "input"))
      (node (ref "SV2") (pin "9") (pinfunction "9_9") (pintype "passive"))
    )
    (net (code "97") (name "RE7") (class "Default")
      (node (ref "IC3") (pin "5") (pinfunction "BI_5") (pintype "input"))
      (node (ref "SV2") (pin "10") (pinfunction "10_10") (pintype "passive"))
    )
    (net (code "98") (name "RF1") (class "Default")
      (node (ref "IC3") (pin "7") (pinfunction "CI_7") (pintype "input"))
      (node (ref "SV2") (pin "11") (pinfunction "11_11") (pintype "passive"))
    )
    (net (code "99") (name "RG9") (class "Default")
      (node (ref "IC7") (pin "14") (pinfunction "Y3_14") (pintype "tri_state"))
      (node (ref "SV2") (pin "12") (pinfunction "12_12") (pintype "passive"))
    )
    (net (code "100") (name "RXD") (class "Default")
      (node (ref "UEXT") (pin "4") (pinfunction "4_4") (pintype "passive"))
    )
    (net (code "101") (name "SCK{slash}LED1") (class "Default")
      (node (ref "U2") (pin "8") (pinfunction "SCK_8") (pintype "input"))
      (node (ref "UEXT") (pin "9") (pinfunction "9_9") (pintype "passive"))
    )
    (net (code "102") (name "SCL") (class "Default")
      (node (ref "UEXT") (pin "5") (pinfunction "5_5") (pintype "passive"))
    )
    (net (code "103") (name "SDA") (class "Default")
      (node (ref "UEXT") (pin "6") (pinfunction "6_6") (pintype "passive"))
    )
    (net (code "104") (name "SPINDLE_ANALOG") (class "Default")
      (node (ref "C36") (pin "2") (pinfunction "2_2") (pintype "passive"))
      (node (ref "IC8") (pin "1") (pinfunction "OUT_1") (pintype "output"))
      (node (ref "JP39") (pin "1") (pinfunction "1_1") (pintype "passive"))
      (node (ref "R19") (pin "1") (pinfunction "1_1") (pintype "passive"))
      (node (ref "X3") (pin "1") (pinfunction "1_1") (pintype "passive"))
    )
    (net (code "105") (name "SPINDLE_ENABLE") (class "Default")
      (node (ref "IC3") (pin "10") (pinfunction "DO_10") (pintype "output"))
      (node (ref "X1") (pin "17") (pinfunction "17_17") (pintype "passive"))
    )
    (net (code "106") (name "SPINDLE_PWM") (class "Default")
      (node (ref "IC3") (pin "12") (pinfunction "EO_12") (pintype "output"))
      (node (ref "X1") (pin "1") (pinfunction "1_1") (pintype "passive"))
    )
    (net (code "107") (name "STEPPER_ENABLE") (class "Default")
      (node (ref "IC3") (pin "2") (pinfunction "AO_2") (pintype "output"))
      (node (ref "X1") (pin "14") (pinfunction "14_14") (pintype "passive"))
    )
    (net (code "108") (name "STEP_A") (class "Default")
      (node (ref "IC3") (pin "4") (pinfunction "BO_4") (pintype "output"))
      (node (ref "X1") (pin "8") (pinfunction "8_8") (pintype "passive"))
    )
    (net (code "109") (name "STEP_X") (class "Default")
      (node (ref "IC2") (pin "2") (pinfunction "AO_2") (pintype "output"))
      (node (ref "X1") (pin "2") (pinfunction "2_2") (pintype "passive"))
    )
    (net (code "110") (name "STEP_Y") (class "Default")
      (node (ref "IC2") (pin "6") (pinfunction "CO_6") (pintype "output"))
      (node (ref "X1") (pin "4") (pinfunction "4_4") (pintype "passive"))
    )
    (net (code "111") (name "STEP_Z") (class "Default")
      (node (ref "IC2") (pin "12") (pinfunction "EO_12") (pintype "output"))
      (node (ref "X1") (pin "6") (pinfunction "6_6") (pintype "passive"))
    )
    (net (code "112") (name "TXD") (class "Default")
      (node (ref "UEXT") (pin "3") (pinfunction "3_3") (pintype "passive"))
    )
    (net (code "113") (name "UEXT_#CS") (class "Default")
      (node (ref "R124") (pin "2") (pinfunction "2_2") (pintype "passive"))
      (node (ref "U2") (pin "9") (pinfunction "CS_9") (pintype "input"))
      (node (ref "UEXT") (pin "10") (pinfunction "10_10") (pintype "passive"))
    )
    (net (code "114") (name "unconnected-(IC3A-FO-Pad15)") (class "Default")
      (node (ref "IC3") (pin "15") (pinfunction "FO_15") (pintype "output"))
    )
    (net (code "115") (name "unconnected-(IC4A-BO-Pad4)") (class "Default")
      (node (ref "IC4") (pin "4") (pinfunction "BO_4") (pintype "output"))
    )
    (net (code "116") (name "unconnected-(IC4A-CO-Pad6)") (class "Default")
      (node (ref "IC4") (pin "6") (pinfunction "CO_6") (pintype "output"))
    )
    (net (code "117") (name "unconnected-(IC4A-DO-Pad10)") (class "Default")
      (node (ref "IC4") (pin "10") (pinfunction "DO_10") (pintype "output"))
    )
    (net (code "118") (name "unconnected-(IC4A-EO-Pad12)") (class "Default")
      (node (ref "IC4") (pin "12") (pinfunction "EO_12") (pintype "output"))
    )
    (net (code "119") (name "unconnected-(IC4A-FO-Pad15)") (class "Default")
      (node (ref "IC4") (pin "15") (pinfunction "FO_15") (pintype "output"))
    )
    (net (code "120") (name "unconnected-(IC7B-Y4-Pad3)") (class "Default")
      (node (ref "IC7") (pin "3") (pinfunction "Y4_3") (pintype "tri_state"))
    )
    (net (code "121") (name "unconnected-(U2-CLKOUT-Pad3)") (class "Default")
      (node (ref "U2") (pin "3") (pinfunction "CLKOUT_3") (pintype "output"))
    )
    (net (code "122") (name "unconnected-(UEXT-Pad1)") (class "Default")
      (node (ref "UEXT") (pin "1") (pinfunction "1_1") (pintype "passive"))
    )
    (net (code "123") (name "~{PROBE_ISOLATED}") (class "Default")
      (node (ref "IC7") (pin "15") (pinfunction "A3_15") (pintype "input"))
      (node (ref "OK4") (pin "14") (pinfunction "COL_14") (pintype "passive"))
      (node (ref "R13") (pin "1") (pinfunction "1_1") (pintype "passive"))
    )
  )
)
